# axiom_beta_plugin_module_TE0714_SDI_v0_6.net
KiCad netlist of a schematic drawn in EAGLE
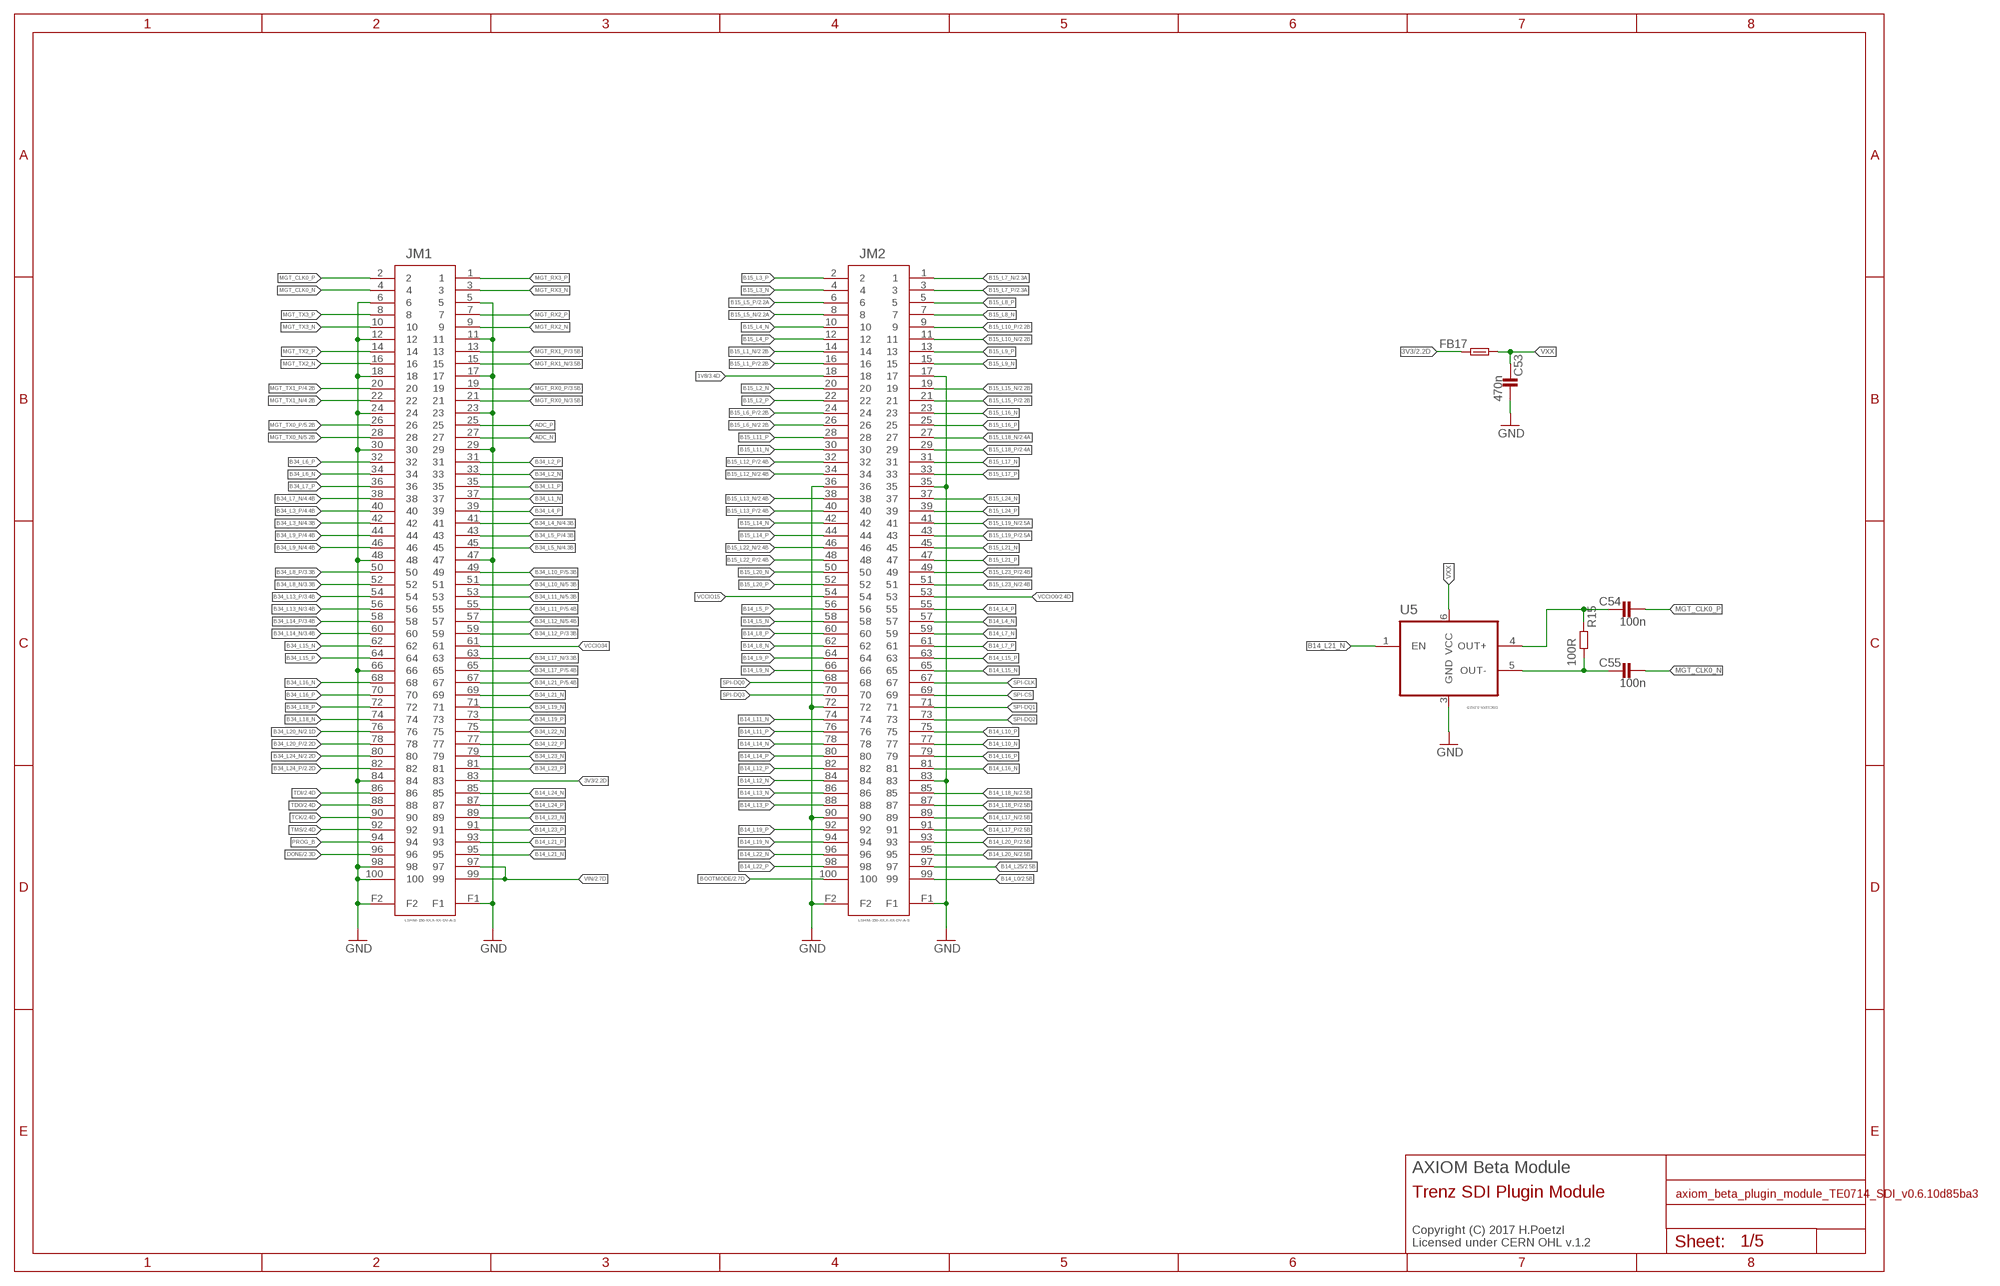
[diagram p0: schematic, sheet 1]
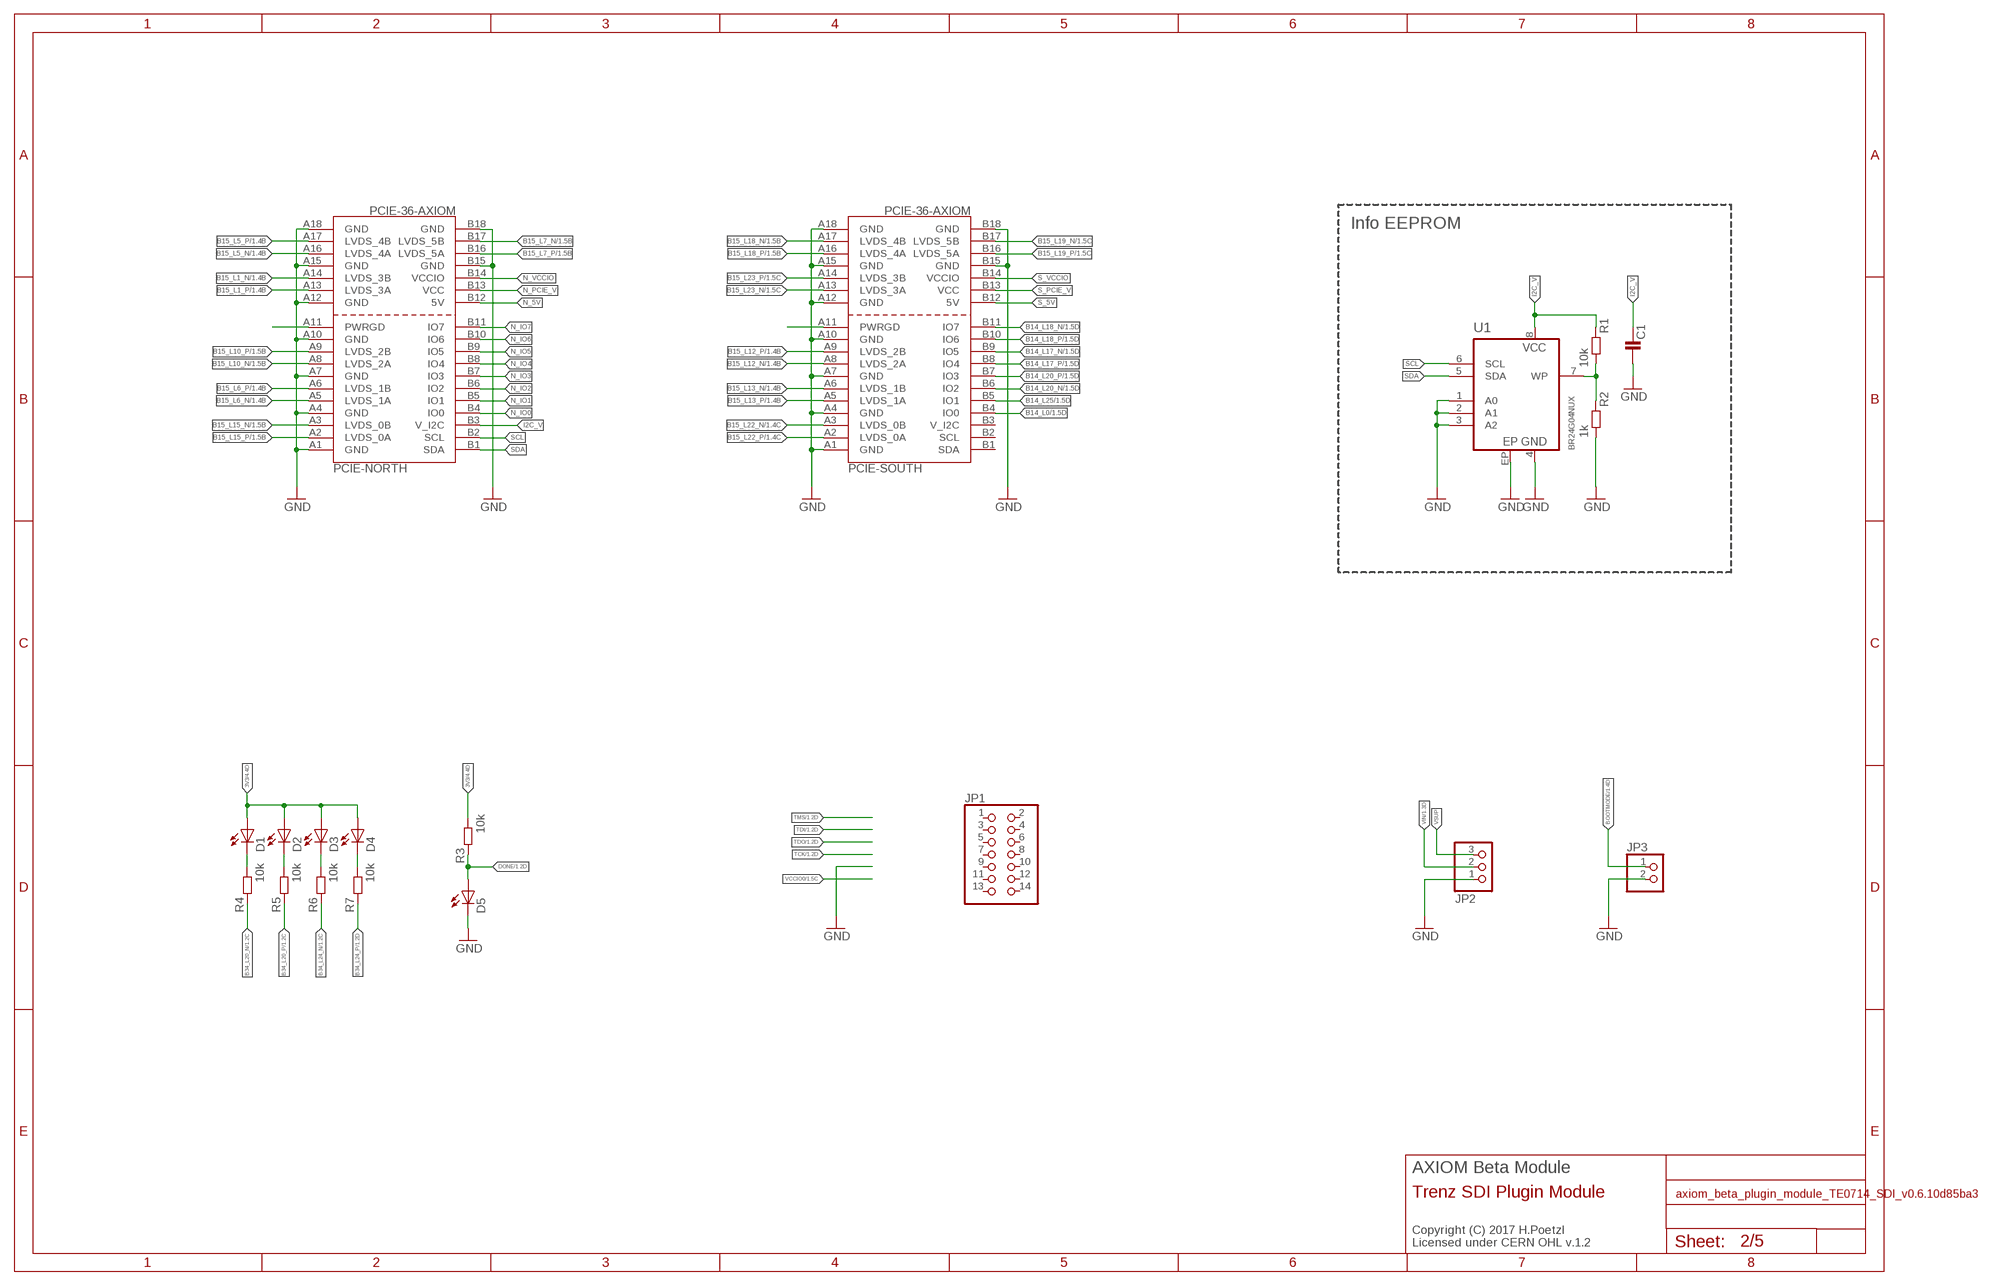
[diagram p1: schematic, sheet 2]
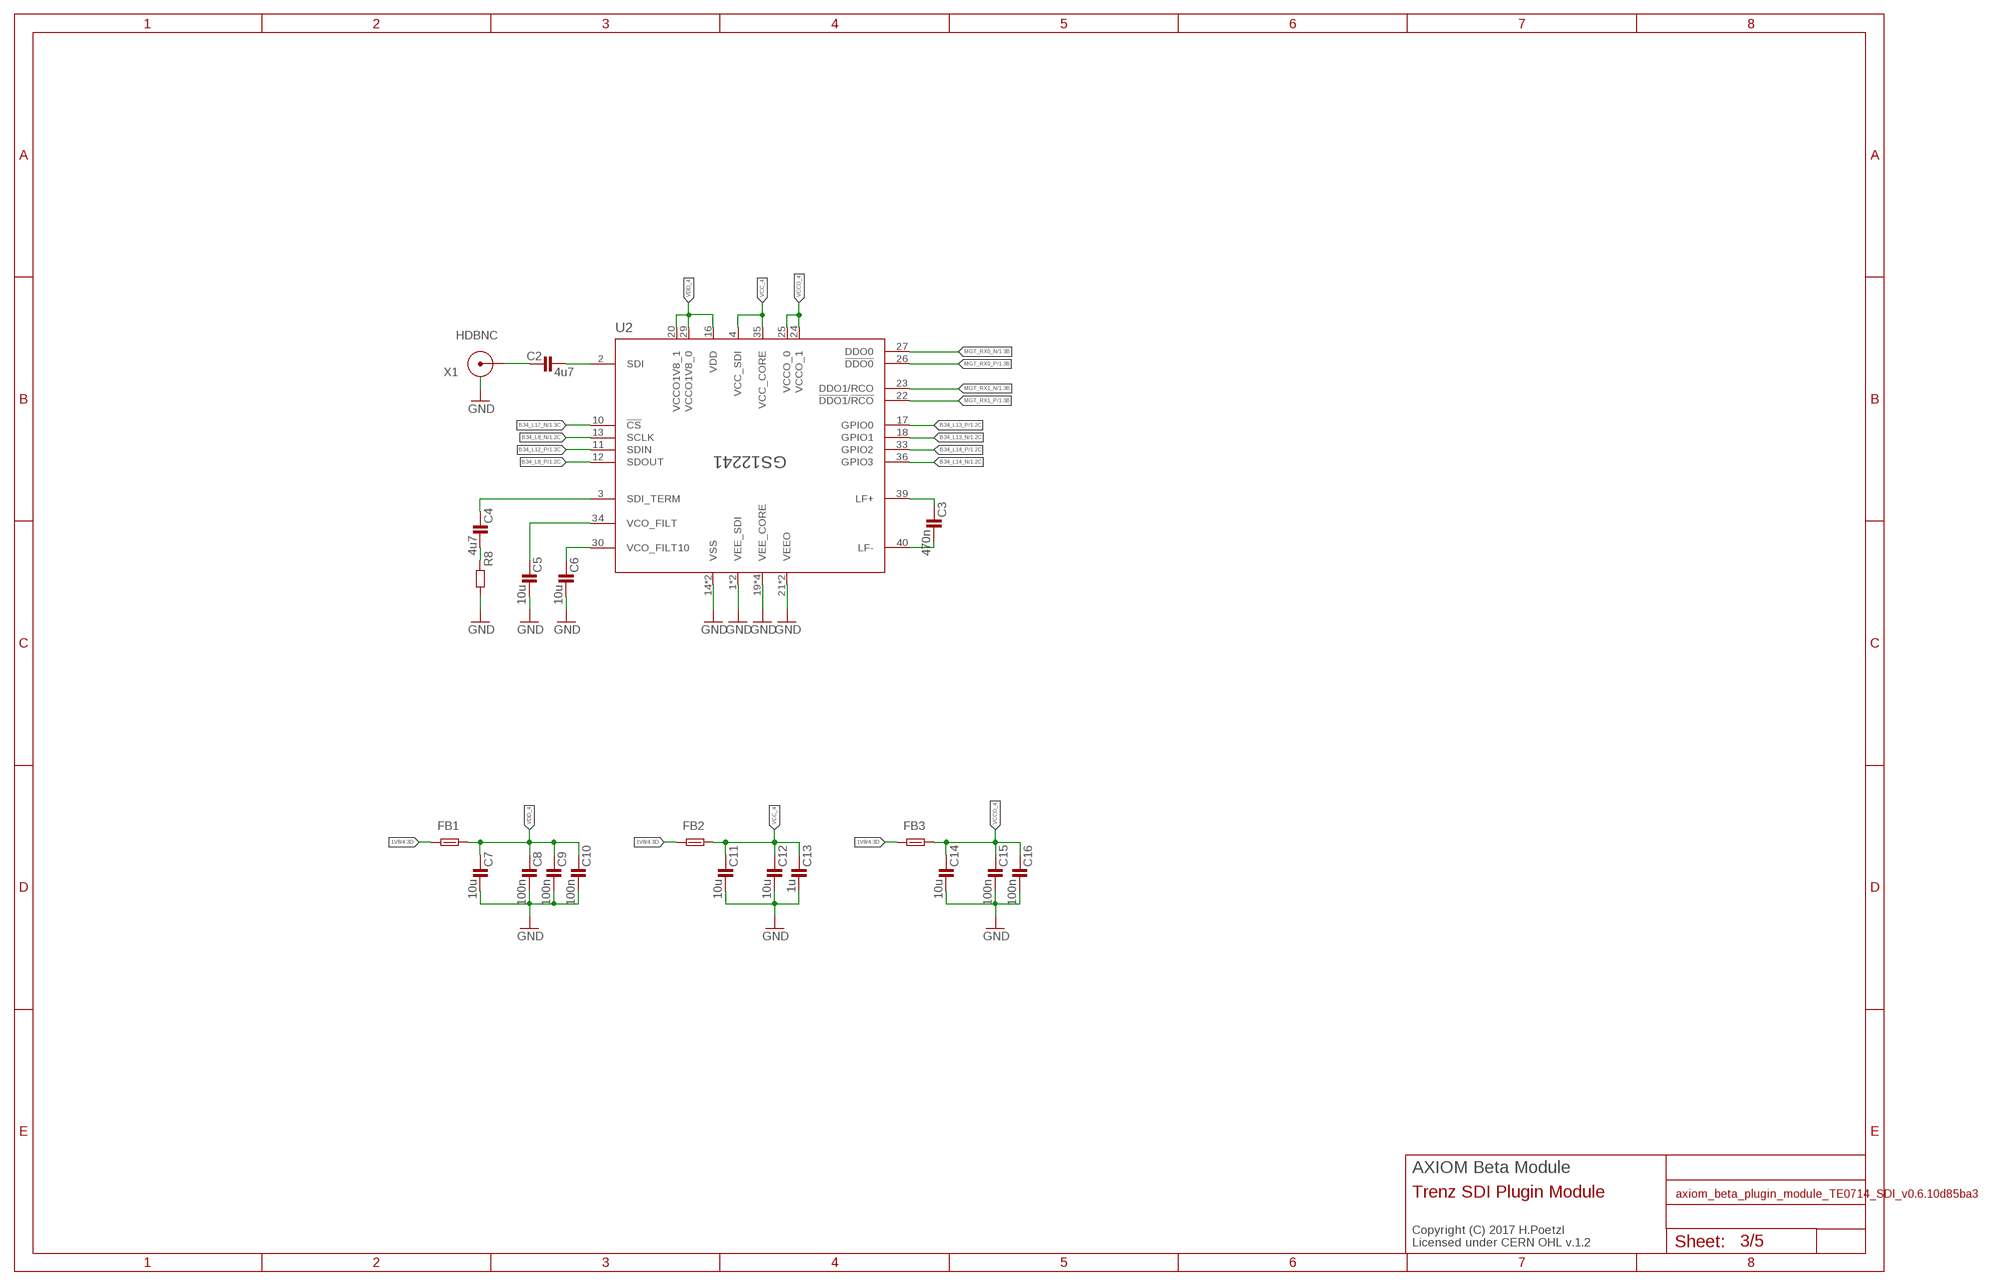
[diagram p2: schematic, sheet 3]
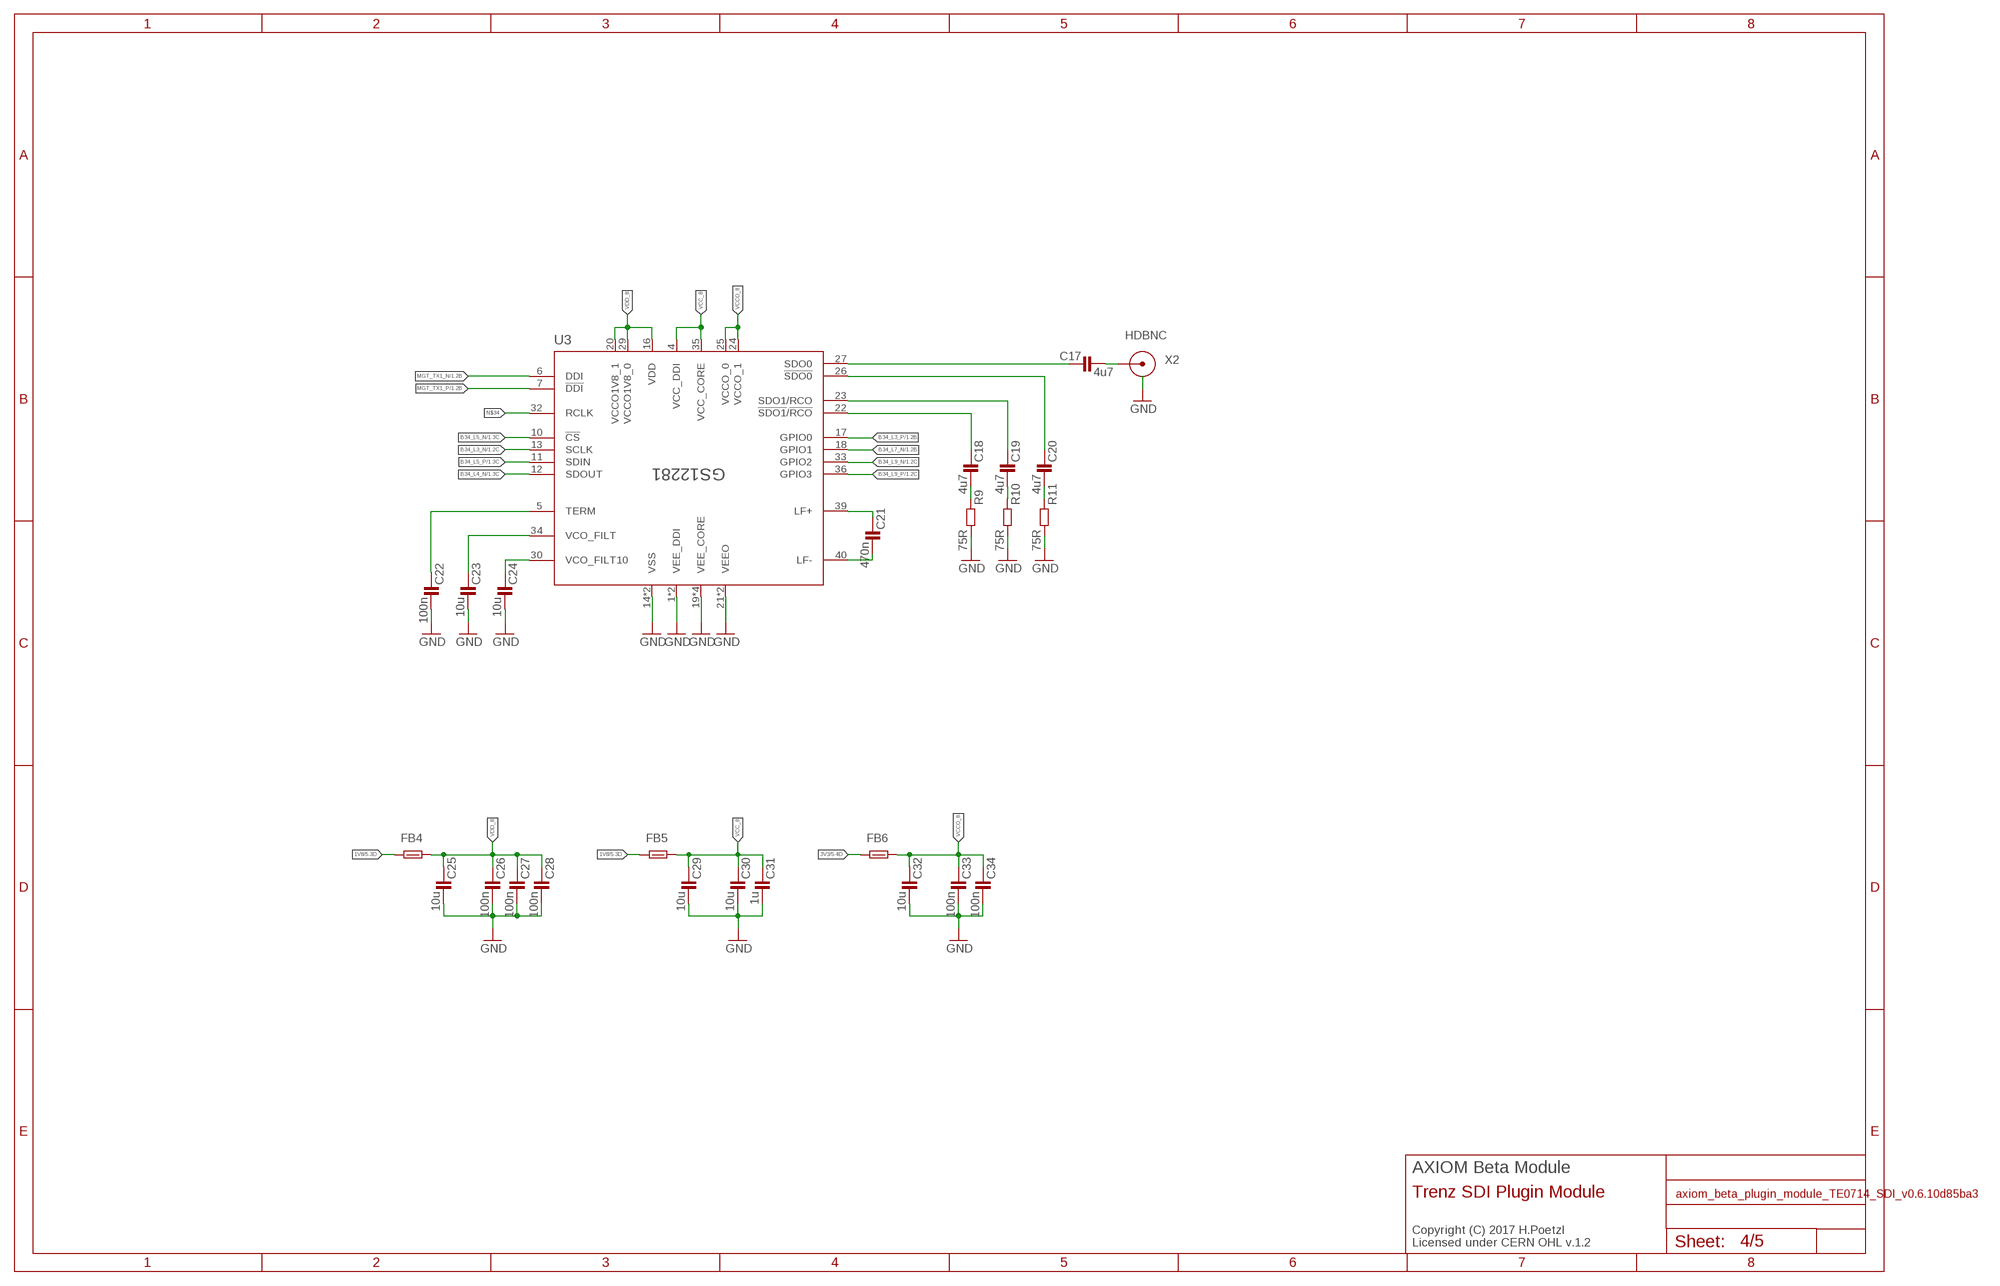
[diagram p3: schematic, sheet 4]
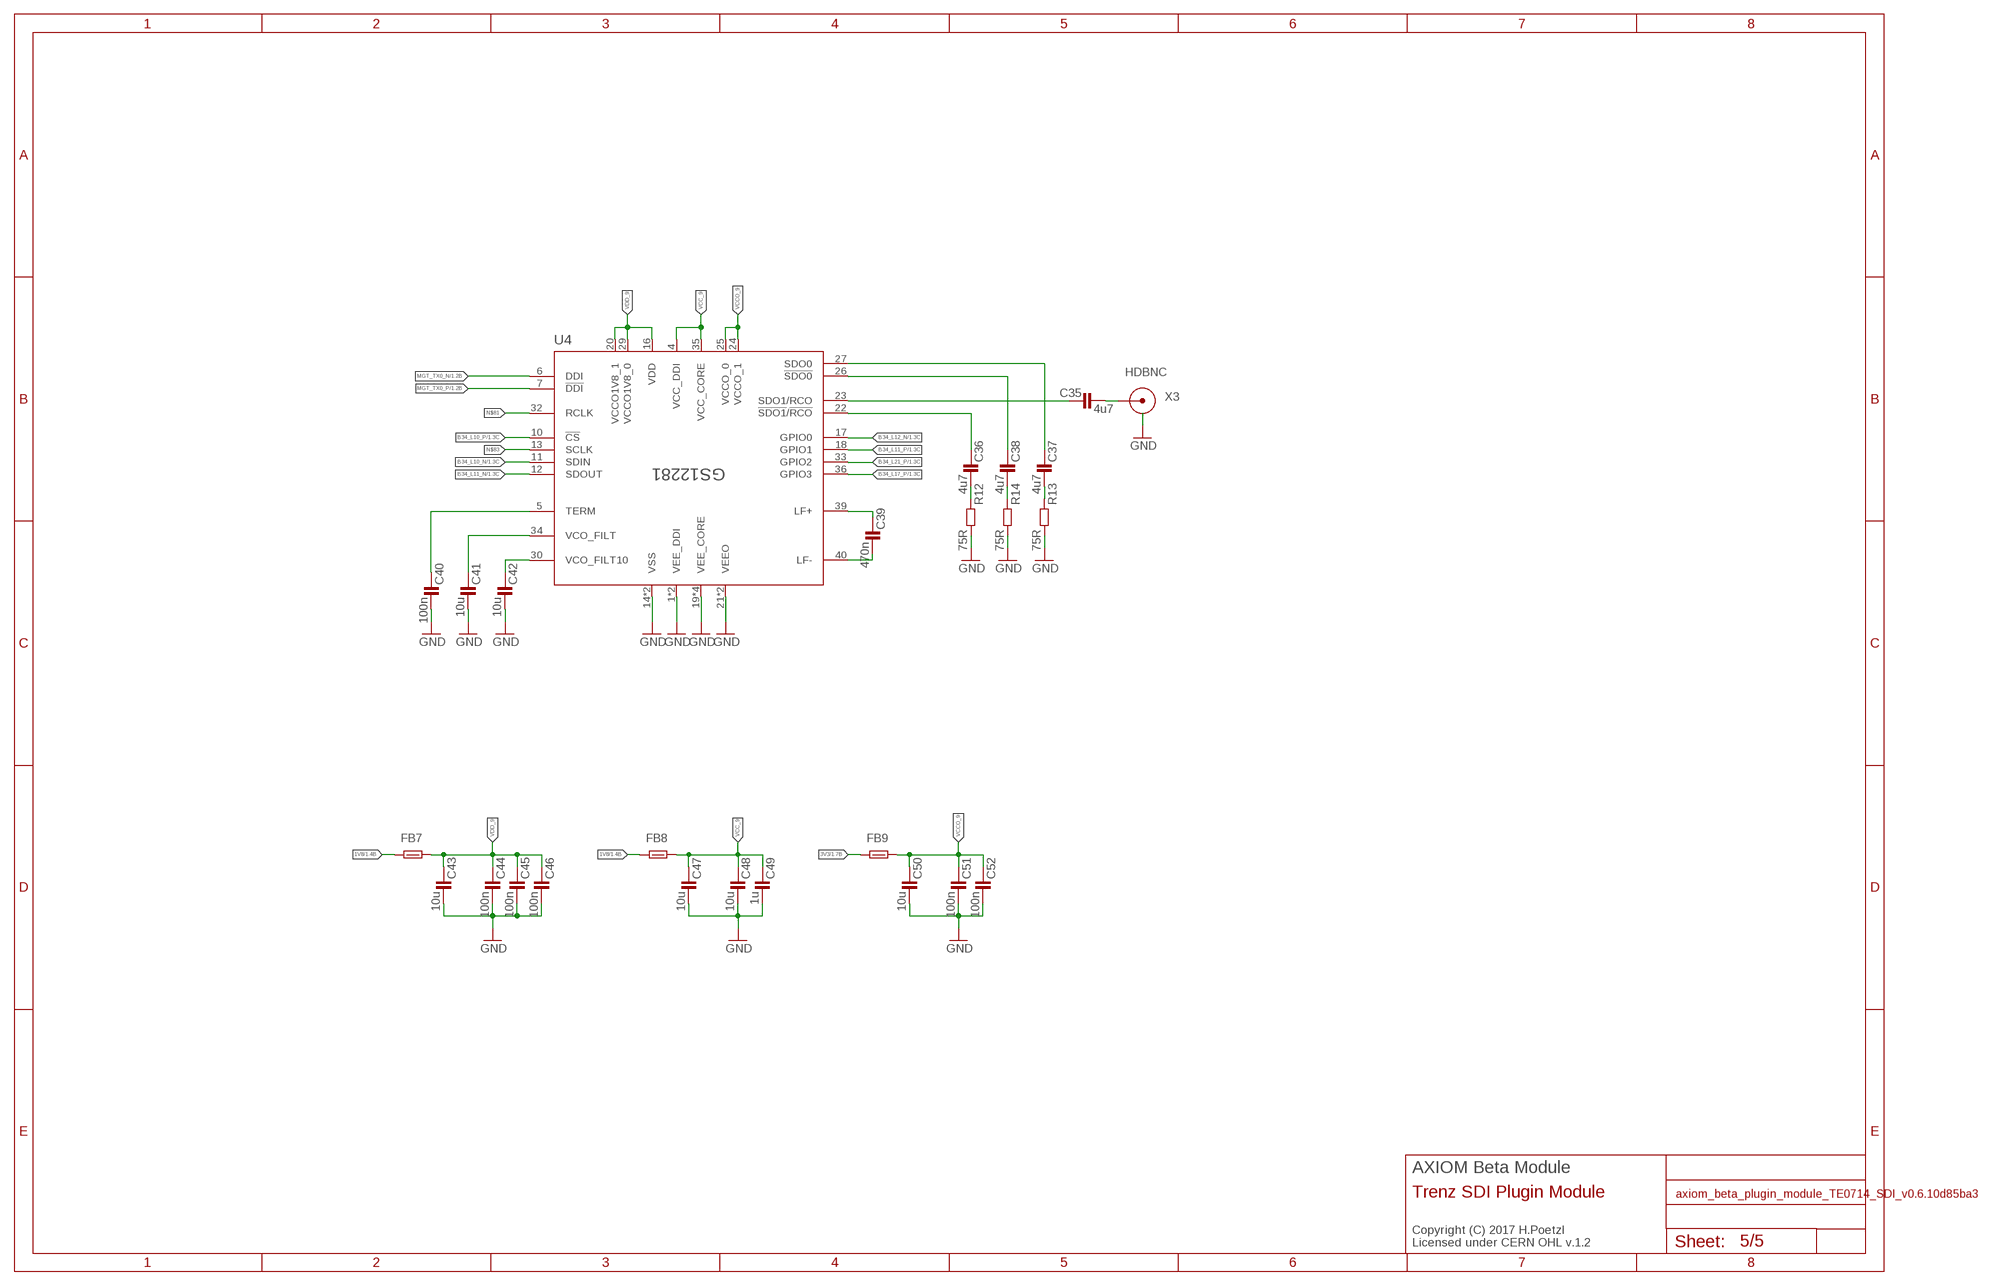
[diagram p4: schematic, sheet 5]

(export (version "E")
  (design (tool "Eeschema 10.0.6"))
  (components
    (comp (ref "C2")
      (value "4u7")
      (footprint "eagle-import:0402-C")
      (libsource (lib "eagle-import") (part "C0402-C"))
    )
    (comp (ref "C3")
      (value "470n")
      (footprint "eagle-import:0201-C")
      (libsource (lib "eagle-import") (part "C0201-C"))
    )
    (comp (ref "C4")
      (value "4u7")
      (footprint "eagle-import:0402-C")
      (libsource (lib "eagle-import") (part "C0402-C"))
    )
    (comp (ref "C5")
      (value "10u")
      (footprint "eagle-import:0201-C")
      (libsource (lib "eagle-import") (part "C0201-C"))
    )
    (comp (ref "C6")
      (value "10u")
      (footprint "eagle-import:0402-C")
      (libsource (lib "eagle-import") (part "C0402-C"))
    )
    (comp (ref "C7")
      (value "10u")
      (footprint "eagle-import:0402-C")
      (libsource (lib "eagle-import") (part "C0402-C"))
    )
    (comp (ref "C8")
      (value "100n")
      (footprint "eagle-import:0201-C")
      (libsource (lib "eagle-import") (part "C0201-C"))
    )
    (comp (ref "C9")
      (value "100n")
      (footprint "eagle-import:0201-C")
      (libsource (lib "eagle-import") (part "C0201-C"))
    )
    (comp (ref "C10")
      (value "100n")
      (footprint "eagle-import:0201-C")
      (libsource (lib "eagle-import") (part "C0201-C"))
    )
    (comp (ref "C11")
      (value "10u")
      (footprint "eagle-import:0402-C")
      (libsource (lib "eagle-import") (part "C0402-C"))
    )
    (comp (ref "C12")
      (value "10u")
      (footprint "eagle-import:0402-C")
      (libsource (lib "eagle-import") (part "C0402-C"))
    )
    (comp (ref "C13")
      (value "1u")
      (footprint "eagle-import:0201-C")
      (libsource (lib "eagle-import") (part "C0201-C"))
    )
    (comp (ref "C14")
      (value "10u")
      (footprint "eagle-import:0402-C")
      (libsource (lib "eagle-import") (part "C0402-C"))
    )
    (comp (ref "C15")
      (value "100n")
      (footprint "eagle-import:0201-C")
      (libsource (lib "eagle-import") (part "C0201-C"))
    )
    (comp (ref "C16")
      (value "100n")
      (footprint "eagle-import:0201-C")
      (libsource (lib "eagle-import") (part "C0201-C"))
    )
    (comp (ref "FB1")
      (value "FB0402-C")
      (footprint "eagle-import:0402-C")
      (libsource (lib "eagle-import") (part "FB0402-C"))
    )
    (comp (ref "FB2")
      (value "FB0402-C")
      (footprint "eagle-import:0402-C")
      (libsource (lib "eagle-import") (part "FB0402-C"))
    )
    (comp (ref "FB3")
      (value "FB0402-C")
      (footprint "eagle-import:0402-C")
      (libsource (lib "eagle-import") (part "FB0402-C"))
    )
    (comp (ref "R8")
      (value "R0201-C")
      (footprint "eagle-import:0201-C")
      (libsource (lib "eagle-import") (part "R0201-C"))
    )
    (comp (ref "U2")
      (value "GS12241")
      (footprint "eagle-import:UQFN40P600X400X100-41N")
      (libsource (lib "eagle-import") (part "GS12241"))
    )
    (comp (ref "X1")
      (value "HDBNC")
      (footprint "eagle-import:HDBNC_EDGE_2SIDE")
      (libsource (lib "eagle-import") (part "HDBNC"))
    )
    (comp (ref "C1")
      (value "C0402-B")
      (footprint "eagle-import:0402-B")
      (libsource (lib "eagle-import") (part "C0402-B"))
    )
    (comp (ref "D1")
      (value "LED")
      (footprint "eagle-import:SMARTLED-TTW")
      (libsource (lib "eagle-import") (part "LED"))
    )
    (comp (ref "D2")
      (value "LED")
      (footprint "eagle-import:SMARTLED-TTW")
      (libsource (lib "eagle-import") (part "LED"))
    )
    (comp (ref "D3")
      (value "LED")
      (footprint "eagle-import:SMARTLED-TTW")
      (libsource (lib "eagle-import") (part "LED"))
    )
    (comp (ref "D4")
      (value "LED")
      (footprint "eagle-import:SMARTLED-TTW")
      (libsource (lib "eagle-import") (part "LED"))
    )
    (comp (ref "D5")
      (value "LED")
      (footprint "eagle-import:SMARTLED-TTW")
      (libsource (lib "eagle-import") (part "LED"))
    )
    (comp (ref "JP1")
      (value "PINHD-2X07_2.00")
      (footprint "eagle-import:2X07M")
      (libsource (lib "eagle-import") (part "PINHD-2X07_2.00"))
    )
    (comp (ref "JP2")
      (value "PINHD-1X03_2.54-90°-S")
      (footprint "eagle-import:1X03_90-S")
      (libsource (lib "eagle-import") (part "PINHD-1X03_2.54-90°-S"))
    )
    (comp (ref "JP3")
      (value "PINHD-1X02_2.54-S")
      (footprint "eagle-import:1X02-S")
      (libsource (lib "eagle-import") (part "PINHD-1X02_2.54-S"))
    )
    (comp (ref "PCIE-NORTH")
      (value "PCIE-36-AXIOM")
      (footprint "eagle-import:PCIE-36-AXIOM")
      (libsource (lib "eagle-import") (part "PCIE-36-AXIOM"))
    )
    (comp (ref "PCIE-SOUTH")
      (value "PCIE-36-AXIOM")
      (footprint "eagle-import:PCIE-36-AXIOM")
      (libsource (lib "eagle-import") (part "PCIE-36-AXIOM"))
    )
    (comp (ref "R1")
      (value "10k")
      (footprint "eagle-import:0402-B")
      (libsource (lib "eagle-import") (part "R0402-B"))
    )
    (comp (ref "R2")
      (value "1k")
      (footprint "eagle-import:0402-B")
      (libsource (lib "eagle-import") (part "R0402-B"))
    )
    (comp (ref "R3")
      (value "10k")
      (footprint "eagle-import:0402-C")
      (libsource (lib "eagle-import") (part "R0402-C"))
    )
    (comp (ref "R4")
      (value "10k")
      (footprint "eagle-import:0402-C")
      (libsource (lib "eagle-import") (part "R0402-C"))
    )
    (comp (ref "R5")
      (value "10k")
      (footprint "eagle-import:0402-C")
      (libsource (lib "eagle-import") (part "R0402-C"))
    )
    (comp (ref "R6")
      (value "10k")
      (footprint "eagle-import:0402-C")
      (libsource (lib "eagle-import") (part "R0402-C"))
    )
    (comp (ref "R7")
      (value "10k")
      (footprint "eagle-import:0402-C")
      (libsource (lib "eagle-import") (part "R0402-C"))
    )
    (comp (ref "U1")
      (value "BR24G04NUX")
      (footprint "eagle-import:DFN200X300X100-9N")
      (libsource (lib "eagle-import") (part "BR24G04NUX"))
    )
    (comp (ref "C17")
      (value "4u7")
      (footprint "eagle-import:0402-C")
      (libsource (lib "eagle-import") (part "C0402-C"))
    )
    (comp (ref "C18")
      (value "4u7")
      (footprint "eagle-import:0402-C")
      (libsource (lib "eagle-import") (part "C0402-C"))
    )
    (comp (ref "C19")
      (value "4u7")
      (footprint "eagle-import:0402-C")
      (libsource (lib "eagle-import") (part "C0402-C"))
    )
    (comp (ref "C20")
      (value "4u7")
      (footprint "eagle-import:0402-C")
      (libsource (lib "eagle-import") (part "C0402-C"))
    )
    (comp (ref "C21")
      (value "470n")
      (footprint "eagle-import:0201-C")
      (libsource (lib "eagle-import") (part "C0201-C"))
    )
    (comp (ref "C22")
      (value "100n")
      (footprint "eagle-import:0201-C")
      (libsource (lib "eagle-import") (part "C0201-C"))
    )
    (comp (ref "C23")
      (value "10u")
      (footprint "eagle-import:0201-C")
      (libsource (lib "eagle-import") (part "C0201-C"))
    )
    (comp (ref "C24")
      (value "10u")
      (footprint "eagle-import:0402-C")
      (libsource (lib "eagle-import") (part "C0402-C"))
    )
    (comp (ref "C25")
      (value "10u")
      (footprint "eagle-import:0402-C")
      (libsource (lib "eagle-import") (part "C0402-C"))
    )
    (comp (ref "C26")
      (value "100n")
      (footprint "eagle-import:0201-C")
      (libsource (lib "eagle-import") (part "C0201-C"))
    )
    (comp (ref "C27")
      (value "100n")
      (footprint "eagle-import:0201-C")
      (libsource (lib "eagle-import") (part "C0201-C"))
    )
    (comp (ref "C28")
      (value "100n")
      (footprint "eagle-import:0201-C")
      (libsource (lib "eagle-import") (part "C0201-C"))
    )
    (comp (ref "C29")
      (value "10u")
      (footprint "eagle-import:0402-C")
      (libsource (lib "eagle-import") (part "C0402-C"))
    )
    (comp (ref "C30")
      (value "10u")
      (footprint "eagle-import:0402-C")
      (libsource (lib "eagle-import") (part "C0402-C"))
    )
    (comp (ref "C31")
      (value "1u")
      (footprint "eagle-import:0201-C")
      (libsource (lib "eagle-import") (part "C0201-C"))
    )
    (comp (ref "C32")
      (value "10u")
      (footprint "eagle-import:0402-C")
      (libsource (lib "eagle-import") (part "C0402-C"))
    )
    (comp (ref "C33")
      (value "100n")
      (footprint "eagle-import:0201-C")
      (libsource (lib "eagle-import") (part "C0201-C"))
    )
    (comp (ref "C34")
      (value "100n")
      (footprint "eagle-import:0201-C")
      (libsource (lib "eagle-import") (part "C0201-C"))
    )
    (comp (ref "FB4")
      (value "FB0402-C")
      (footprint "eagle-import:0402-C")
      (libsource (lib "eagle-import") (part "FB0402-C"))
    )
    (comp (ref "FB5")
      (value "FB0402-C")
      (footprint "eagle-import:0402-C")
      (libsource (lib "eagle-import") (part "FB0402-C"))
    )
    (comp (ref "FB6")
      (value "FB0402-C")
      (footprint "eagle-import:0402-C")
      (libsource (lib "eagle-import") (part "FB0402-C"))
    )
    (comp (ref "R9")
      (value "75R")
      (footprint "eagle-import:0201-C")
      (libsource (lib "eagle-import") (part "R0201-C"))
    )
    (comp (ref "R10")
      (value "75R")
      (footprint "eagle-import:0201-C")
      (libsource (lib "eagle-import") (part "R0201-C"))
    )
    (comp (ref "R11")
      (value "75R")
      (footprint "eagle-import:0201-C")
      (libsource (lib "eagle-import") (part "R0201-C"))
    )
    (comp (ref "U3")
      (value "GS12281")
      (footprint "eagle-import:UQFN40P600X400X100-41N")
      (libsource (lib "eagle-import") (part "GS12281"))
    )
    (comp (ref "X2")
      (value "HDBNC")
      (footprint "eagle-import:HDBNC_EDGE_2SIDE")
      (libsource (lib "eagle-import") (part "HDBNC"))
    )
    (comp (ref "C35")
      (value "4u7")
      (footprint "eagle-import:0402-C")
      (libsource (lib "eagle-import") (part "C0402-C"))
    )
    (comp (ref "C36")
      (value "4u7")
      (footprint "eagle-import:0402-C")
      (libsource (lib "eagle-import") (part "C0402-C"))
    )
    (comp (ref "C37")
      (value "4u7")
      (footprint "eagle-import:0402-C")
      (libsource (lib "eagle-import") (part "C0402-C"))
    )
    (comp (ref "C38")
      (value "4u7")
      (footprint "eagle-import:0402-C")
      (libsource (lib "eagle-import") (part "C0402-C"))
    )
    (comp (ref "C39")
      (value "470n")
      (footprint "eagle-import:0201-C")
      (libsource (lib "eagle-import") (part "C0201-C"))
    )
    (comp (ref "C40")
      (value "100n")
      (footprint "eagle-import:0201-C")
      (libsource (lib "eagle-import") (part "C0201-C"))
    )
    (comp (ref "C41")
      (value "10u")
      (footprint "eagle-import:0402-C")
      (libsource (lib "eagle-import") (part "C0402-C"))
    )
    (comp (ref "C42")
      (value "10u")
      (footprint "eagle-import:0402-C")
      (libsource (lib "eagle-import") (part "C0402-C"))
    )
    (comp (ref "C43")
      (value "10u")
      (footprint "eagle-import:0402-C")
      (libsource (lib "eagle-import") (part "C0402-C"))
    )
    (comp (ref "C44")
      (value "100n")
      (footprint "eagle-import:0201-C")
      (libsource (lib "eagle-import") (part "C0201-C"))
    )
    (comp (ref "C45")
      (value "100n")
      (footprint "eagle-import:0201-C")
      (libsource (lib "eagle-import") (part "C0201-C"))
    )
    (comp (ref "C46")
      (value "100n")
      (footprint "eagle-import:0201-C")
      (libsource (lib "eagle-import") (part "C0201-C"))
    )
    (comp (ref "C47")
      (value "10u")
      (footprint "eagle-import:0402-C")
      (libsource (lib "eagle-import") (part "C0402-C"))
    )
    (comp (ref "C48")
      (value "10u")
      (footprint "eagle-import:0402-C")
      (libsource (lib "eagle-import") (part "C0402-C"))
    )
    (comp (ref "C49")
      (value "1u")
      (footprint "eagle-import:0201-C")
      (libsource (lib "eagle-import") (part "C0201-C"))
    )
    (comp (ref "C50")
      (value "10u")
      (footprint "eagle-import:0402-C")
      (libsource (lib "eagle-import") (part "C0402-C"))
    )
    (comp (ref "C51")
      (value "100n")
      (footprint "eagle-import:0201-C")
      (libsource (lib "eagle-import") (part "C0201-C"))
    )
    (comp (ref "C52")
      (value "100n")
      (footprint "eagle-import:0201-C")
      (libsource (lib "eagle-import") (part "C0201-C"))
    )
    (comp (ref "FB7")
      (value "FB0402-C")
      (footprint "eagle-import:0402-C")
      (libsource (lib "eagle-import") (part "FB0402-C"))
    )
    (comp (ref "FB8")
      (value "FB0402-C")
      (footprint "eagle-import:0402-C")
      (libsource (lib "eagle-import") (part "FB0402-C"))
    )
    (comp (ref "FB9")
      (value "FB0402-C")
      (footprint "eagle-import:0402-C")
      (libsource (lib "eagle-import") (part "FB0402-C"))
    )
    (comp (ref "R12")
      (value "75R")
      (footprint "eagle-import:0201-C")
      (libsource (lib "eagle-import") (part "R0201-C"))
    )
    (comp (ref "R13")
      (value "75R")
      (footprint "eagle-import:0201-C")
      (libsource (lib "eagle-import") (part "R0201-C"))
    )
    (comp (ref "R14")
      (value "75R")
      (footprint "eagle-import:0201-C")
      (libsource (lib "eagle-import") (part "R0201-C"))
    )
    (comp (ref "U4")
      (value "GS12281")
      (footprint "eagle-import:UQFN40P600X400X100-41N")
      (libsource (lib "eagle-import") (part "GS12281"))
    )
    (comp (ref "X3")
      (value "HDBNC")
      (footprint "eagle-import:HDBNC_EDGE_2SIDE")
      (libsource (lib "eagle-import") (part "HDBNC"))
    )
    (comp (ref "C53")
      (value "470n")
      (footprint "eagle-import:0402-C")
      (libsource (lib "eagle-import") (part "C0402-C"))
    )
    (comp (ref "C54")
      (value "100n")
      (footprint "eagle-import:0201-C")
      (libsource (lib "eagle-import") (part "C0201-C"))
    )
    (comp (ref "C55")
      (value "100n")
      (footprint "eagle-import:0201-C")
      (libsource (lib "eagle-import") (part "C0201-C"))
    )
    (comp (ref "FB17")
      (value "FB0402-C")
      (footprint "eagle-import:0402-C")
      (libsource (lib "eagle-import") (part "FB0402-C"))
    )
    (comp (ref "JM1")
      (value "LSHM-150-XX.X-XX-DV-A-S")
      (footprint "eagle-import:LSHM-150-XX.X-XX-DV-A-S")
      (libsource (lib "eagle-import") (part "LSHM-150-XX.X-XX-DV-A-S"))
    )
    (comp (ref "JM2")
      (value "LSHM-150-XX.X-XX-DV-A-S")
      (footprint "eagle-import:LSHM-150-XX.X-XX-DV-A-S")
      (libsource (lib "eagle-import") (part "LSHM-150-XX.X-XX-DV-A-S"))
    )
    (comp (ref "R15")
      (value "100R")
      (footprint "eagle-import:0201-C")
      (libsource (lib "eagle-import") (part "R0201-C"))
    )
    (comp (ref "U5")
      (value "DSC11XX-3.2X2.5")
      (footprint "eagle-import:3.2X2.5")
      (libsource (lib "eagle-import") (part "DSC11XX-3.2X2.5"))
    )
  )
  (nets
    (net (code "1") (name "1V8") (class "Default")
      (node (ref "FB1") (pin "1") (pinfunction "1_1") (pintype "passive"))
      (node (ref "FB2") (pin "1") (pinfunction "1_1") (pintype "passive"))
      (node (ref "FB3") (pin "1") (pinfunction "1_1") (pintype "passive"))
      (node (ref "FB4") (pin "1") (pinfunction "1_1") (pintype "passive"))
      (node (ref "FB5") (pin "1") (pinfunction "1_1") (pintype "passive"))
      (node (ref "FB7") (pin "1") (pinfunction "1_1") (pintype "passive"))
      (node (ref "FB8") (pin "1") (pinfunction "1_1") (pintype "passive"))
      (node (ref "JM2") (pin "18") (pinfunction "18_18") (pintype "bidirectional"))
    )
    (net (code "2") (name "3V3") (class "Default")
      (node (ref "D1") (pin "A@1") (pinfunction "A_A@1") (pintype "passive"))
      (node (ref "D2") (pin "A@1") (pinfunction "A_A@1") (pintype "passive"))
      (node (ref "D3") (pin "A@1") (pinfunction "A_A@1") (pintype "passive"))
      (node (ref "D4") (pin "A@1") (pinfunction "A_A@1") (pintype "passive"))
      (node (ref "FB17") (pin "1") (pinfunction "1_1") (pintype "passive"))
      (node (ref "FB6") (pin "1") (pinfunction "1_1") (pintype "passive"))
      (node (ref "FB9") (pin "1") (pinfunction "1_1") (pintype "passive"))
      (node (ref "JM1") (pin "83") (pinfunction "83_83") (pintype "bidirectional"))
      (node (ref "R3") (pin "2") (pinfunction "2_2") (pintype "passive"))
    )
    (net (code "3") (name "ADC_N") (class "Default")
      (node (ref "JM1") (pin "27") (pinfunction "27_27") (pintype "bidirectional"))
    )
    (net (code "4") (name "ADC_P") (class "Default")
      (node (ref "JM1") (pin "25") (pinfunction "25_25") (pintype "bidirectional"))
    )
    (net (code "5") (name "B14_L0") (class "Default")
      (node (ref "JM2") (pin "99") (pinfunction "99_99") (pintype "bidirectional"))
      (node (ref "PCIE-SOUTH") (pin "B4") (pinfunction "IO0_B4") (pintype "passive"))
    )
    (net (code "6") (name "B14_L4_N") (class "Default")
      (node (ref "JM2") (pin "57") (pinfunction "57_57") (pintype "bidirectional"))
    )
    (net (code "7") (name "B14_L4_P") (class "Default")
      (node (ref "JM2") (pin "55") (pinfunction "55_55") (pintype "bidirectional"))
    )
    (net (code "8") (name "B14_L5_N") (class "Default")
      (node (ref "JM2") (pin "58") (pinfunction "58_58") (pintype "bidirectional"))
    )
    (net (code "9") (name "B14_L5_P") (class "Default")
      (node (ref "JM2") (pin "56") (pinfunction "56_56") (pintype "bidirectional"))
    )
    (net (code "10") (name "B14_L7_N") (class "Default")
      (node (ref "JM2") (pin "59") (pinfunction "59_59") (pintype "bidirectional"))
    )
    (net (code "11") (name "B14_L7_P") (class "Default")
      (node (ref "JM2") (pin "61") (pinfunction "61_61") (pintype "bidirectional"))
    )
    (net (code "12") (name "B14_L8_N") (class "Default")
      (node (ref "JM2") (pin "62") (pinfunction "62_62") (pintype "bidirectional"))
    )
    (net (code "13") (name "B14_L8_P") (class "Default")
      (node (ref "JM2") (pin "60") (pinfunction "60_60") (pintype "bidirectional"))
    )
    (net (code "14") (name "B14_L9_N") (class "Default")
      (node (ref "JM2") (pin "66") (pinfunction "66_66") (pintype "bidirectional"))
    )
    (net (code "15") (name "B14_L9_P") (class "Default")
      (node (ref "JM2") (pin "64") (pinfunction "64_64") (pintype "bidirectional"))
    )
    (net (code "16") (name "B14_L10_N") (class "Default")
      (node (ref "JM2") (pin "77") (pinfunction "77_77") (pintype "bidirectional"))
    )
    (net (code "17") (name "B14_L10_P") (class "Default")
      (node (ref "JM2") (pin "75") (pinfunction "75_75") (pintype "bidirectional"))
    )
    (net (code "18") (name "B14_L11_N") (class "Default")
      (node (ref "JM2") (pin "74") (pinfunction "74_74") (pintype "bidirectional"))
    )
    (net (code "19") (name "B14_L11_P") (class "Default")
      (node (ref "JM2") (pin "76") (pinfunction "76_76") (pintype "bidirectional"))
    )
    (net (code "20") (name "B14_L12_N") (class "Default")
      (node (ref "JM2") (pin "84") (pinfunction "84_84") (pintype "bidirectional"))
    )
    (net (code "21") (name "B14_L12_P") (class "Default")
      (node (ref "JM2") (pin "82") (pinfunction "82_82") (pintype "bidirectional"))
    )
    (net (code "22") (name "B14_L13_N") (class "Default")
      (node (ref "JM2") (pin "86") (pinfunction "86_86") (pintype "bidirectional"))
    )
    (net (code "23") (name "B14_L13_P") (class "Default")
      (node (ref "JM2") (pin "88") (pinfunction "88_88") (pintype "bidirectional"))
    )
    (net (code "24") (name "B14_L14_N") (class "Default")
      (node (ref "JM2") (pin "78") (pinfunction "78_78") (pintype "bidirectional"))
    )
    (net (code "25") (name "B14_L14_P") (class "Default")
      (node (ref "JM2") (pin "80") (pinfunction "80_80") (pintype "bidirectional"))
    )
    (net (code "26") (name "B14_L15_N") (class "Default")
      (node (ref "JM2") (pin "65") (pinfunction "65_65") (pintype "bidirectional"))
    )
    (net (code "27") (name "B14_L15_P") (class "Default")
      (node (ref "JM2") (pin "63") (pinfunction "63_63") (pintype "bidirectional"))
    )
    (net (code "28") (name "B14_L16_N") (class "Default")
      (node (ref "JM2") (pin "81") (pinfunction "81_81") (pintype "bidirectional"))
    )
    (net (code "29") (name "B14_L16_P") (class "Default")
      (node (ref "JM2") (pin "79") (pinfunction "79_79") (pintype "bidirectional"))
    )
    (net (code "30") (name "B14_L17_N") (class "Default")
      (node (ref "JM2") (pin "89") (pinfunction "89_89") (pintype "bidirectional"))
      (node (ref "PCIE-SOUTH") (pin "B9") (pinfunction "IO5_B9") (pintype "passive"))
    )
    (net (code "31") (name "B14_L17_P") (class "Default")
      (node (ref "JM2") (pin "91") (pinfunction "91_91") (pintype "bidirectional"))
      (node (ref "PCIE-SOUTH") (pin "B8") (pinfunction "IO4_B8") (pintype "passive"))
    )
    (net (code "32") (name "B14_L18_N") (class "Default")
      (node (ref "JM2") (pin "85") (pinfunction "85_85") (pintype "bidirectional"))
      (node (ref "PCIE-SOUTH") (pin "B11") (pinfunction "IO7_B11") (pintype "passive"))
    )
    (net (code "33") (name "B14_L18_P") (class "Default")
      (node (ref "JM2") (pin "87") (pinfunction "87_87") (pintype "bidirectional"))
      (node (ref "PCIE-SOUTH") (pin "B10") (pinfunction "IO6_B10") (pintype "passive"))
    )
    (net (code "34") (name "B14_L19_N") (class "Default")
      (node (ref "JM2") (pin "94") (pinfunction "94_94") (pintype "bidirectional"))
    )
    (net (code "35") (name "B14_L19_P") (class "Default")
      (node (ref "JM2") (pin "92") (pinfunction "92_92") (pintype "bidirectional"))
    )
    (net (code "36") (name "B14_L20_N") (class "Default")
      (node (ref "JM2") (pin "95") (pinfunction "95_95") (pintype "bidirectional"))
      (node (ref "PCIE-SOUTH") (pin "B6") (pinfunction "IO2_B6") (pintype "passive"))
    )
    (net (code "37") (name "B14_L20_P") (class "Default")
      (node (ref "JM2") (pin "93") (pinfunction "93_93") (pintype "bidirectional"))
      (node (ref "PCIE-SOUTH") (pin "B7") (pinfunction "IO3_B7") (pintype "passive"))
    )
    (net (code "38") (name "B14_L21_N") (class "Default")
      (node (ref "JM1") (pin "95") (pinfunction "95_95") (pintype "bidirectional"))
      (node (ref "U5") (pin "1") (pinfunction "EN_1") (pintype "input"))
    )
    (net (code "39") (name "B14_L21_P") (class "Default")
      (node (ref "JM1") (pin "93") (pinfunction "93_93") (pintype "bidirectional"))
    )
    (net (code "40") (name "B14_L22_N") (class "Default")
      (node (ref "JM2") (pin "96") (pinfunction "96_96") (pintype "bidirectional"))
    )
    (net (code "41") (name "B14_L22_P") (class "Default")
      (node (ref "JM2") (pin "98") (pinfunction "98_98") (pintype "bidirectional"))
    )
    (net (code "42") (name "B14_L23_N") (class "Default")
      (node (ref "JM1") (pin "89") (pinfunction "89_89") (pintype "bidirectional"))
    )
    (net (code "43") (name "B14_L23_P") (class "Default")
      (node (ref "JM1") (pin "91") (pinfunction "91_91") (pintype "bidirectional"))
    )
    (net (code "44") (name "B14_L24_N") (class "Default")
      (node (ref "JM1") (pin "85") (pinfunction "85_85") (pintype "bidirectional"))
    )
    (net (code "45") (name "B14_L24_P") (class "Default")
      (node (ref "JM1") (pin "87") (pinfunction "87_87") (pintype "bidirectional"))
    )
    (net (code "46") (name "B14_L25") (class "Default")
      (node (ref "JM2") (pin "97") (pinfunction "97_97") (pintype "bidirectional"))
      (node (ref "PCIE-SOUTH") (pin "B5") (pinfunction "IO1_B5") (pintype "passive"))
    )
    (net (code "47") (name "B15_L1_N") (class "Default")
      (node (ref "JM2") (pin "14") (pinfunction "14_14") (pintype "bidirectional"))
      (node (ref "PCIE-NORTH") (pin "A14") (pinfunction "LVDS_3B_A14") (pintype "passive"))
    )
    (net (code "48") (name "B15_L1_P") (class "Default")
      (node (ref "JM2") (pin "16") (pinfunction "16_16") (pintype "bidirectional"))
      (node (ref "PCIE-NORTH") (pin "A13") (pinfunction "LVDS_3A_A13") (pintype "passive"))
    )
    (net (code "49") (name "B15_L2_N") (class "Default")
      (node (ref "JM2") (pin "20") (pinfunction "20_20") (pintype "bidirectional"))
    )
    (net (code "50") (name "B15_L2_P") (class "Default")
      (node (ref "JM2") (pin "22") (pinfunction "22_22") (pintype "bidirectional"))
    )
    (net (code "51") (name "B15_L3_N") (class "Default")
      (node (ref "JM2") (pin "4") (pinfunction "4_4") (pintype "bidirectional"))
    )
    (net (code "52") (name "B15_L3_P") (class "Default")
      (node (ref "JM2") (pin "2") (pinfunction "2_2") (pintype "bidirectional"))
    )
    (net (code "53") (name "B15_L4_N") (class "Default")
      (node (ref "JM2") (pin "10") (pinfunction "10_10") (pintype "bidirectional"))
    )
    (net (code "54") (name "B15_L4_P") (class "Default")
      (node (ref "JM2") (pin "12") (pinfunction "12_12") (pintype "bidirectional"))
    )
    (net (code "55") (name "B15_L5_N") (class "Default")
      (node (ref "JM2") (pin "8") (pinfunction "8_8") (pintype "bidirectional"))
      (node (ref "PCIE-NORTH") (pin "A16") (pinfunction "LVDS_4A_A16") (pintype "passive"))
    )
    (net (code "56") (name "B15_L5_P") (class "Default")
      (node (ref "JM2") (pin "6") (pinfunction "6_6") (pintype "bidirectional"))
      (node (ref "PCIE-NORTH") (pin "A17") (pinfunction "LVDS_4B_A17") (pintype "passive"))
    )
    (net (code "57") (name "B15_L6_N") (class "Default")
      (node (ref "JM2") (pin "26") (pinfunction "26_26") (pintype "bidirectional"))
      (node (ref "PCIE-NORTH") (pin "A5") (pinfunction "LVDS_1A_A5") (pintype "passive"))
    )
    (net (code "58") (name "B15_L6_P") (class "Default")
      (node (ref "JM2") (pin "24") (pinfunction "24_24") (pintype "bidirectional"))
      (node (ref "PCIE-NORTH") (pin "A6") (pinfunction "LVDS_1B_A6") (pintype "passive"))
    )
    (net (code "59") (name "B15_L7_N") (class "Default")
      (node (ref "JM2") (pin "1") (pinfunction "1_1") (pintype "bidirectional"))
      (node (ref "PCIE-NORTH") (pin "B17") (pinfunction "LVDS_5B_B17") (pintype "passive"))
    )
    (net (code "60") (name "B15_L7_P") (class "Default")
      (node (ref "JM2") (pin "3") (pinfunction "3_3") (pintype "bidirectional"))
      (node (ref "PCIE-NORTH") (pin "B16") (pinfunction "LVDS_5A_B16") (pintype "passive"))
    )
    (net (code "61") (name "B15_L8_N") (class "Default")
      (node (ref "JM2") (pin "7") (pinfunction "7_7") (pintype "bidirectional"))
    )
    (net (code "62") (name "B15_L8_P") (class "Default")
      (node (ref "JM2") (pin "5") (pinfunction "5_5") (pintype "bidirectional"))
    )
    (net (code "63") (name "B15_L9_N") (class "Default")
      (node (ref "JM2") (pin "15") (pinfunction "15_15") (pintype "bidirectional"))
    )
    (net (code "64") (name "B15_L9_P") (class "Default")
      (node (ref "JM2") (pin "13") (pinfunction "13_13") (pintype "bidirectional"))
    )
    (net (code "65") (name "B15_L10_N") (class "Default")
      (node (ref "JM2") (pin "11") (pinfunction "11_11") (pintype "bidirectional"))
      (node (ref "PCIE-NORTH") (pin "A8") (pinfunction "LVDS_2A_A8") (pintype "passive"))
    )
    (net (code "66") (name "B15_L10_P") (class "Default")
      (node (ref "JM2") (pin "9") (pinfunction "9_9") (pintype "bidirectional"))
      (node (ref "PCIE-NORTH") (pin "A9") (pinfunction "LVDS_2B_A9") (pintype "passive"))
    )
    (net (code "67") (name "B15_L11_N") (class "Default")
      (node (ref "JM2") (pin "30") (pinfunction "30_30") (pintype "bidirectional"))
    )
    (net (code "68") (name "B15_L11_P") (class "Default")
      (node (ref "JM2") (pin "28") (pinfunction "28_28") (pintype "bidirectional"))
    )
    (net (code "69") (name "B15_L12_N") (class "Default")
      (node (ref "JM2") (pin "34") (pinfunction "34_34") (pintype "bidirectional"))
      (node (ref "PCIE-SOUTH") (pin "A8") (pinfunction "LVDS_2A_A8") (pintype "passive"))
    )
    (net (code "70") (name "B15_L12_P") (class "Default")
      (node (ref "JM2") (pin "32") (pinfunction "32_32") (pintype "bidirectional"))
      (node (ref "PCIE-SOUTH") (pin "A9") (pinfunction "LVDS_2B_A9") (pintype "passive"))
    )
    (net (code "71") (name "B15_L13_N") (class "Default")
      (node (ref "JM2") (pin "38") (pinfunction "38_38") (pintype "bidirectional"))
      (node (ref "PCIE-SOUTH") (pin "A6") (pinfunction "LVDS_1B_A6") (pintype "passive"))
    )
    (net (code "72") (name "B15_L13_P") (class "Default")
      (node (ref "JM2") (pin "40") (pinfunction "40_40") (pintype "bidirectional"))
      (node (ref "PCIE-SOUTH") (pin "A5") (pinfunction "LVDS_1A_A5") (pintype "passive"))
    )
    (net (code "73") (name "B15_L14_N") (class "Default")
      (node (ref "JM2") (pin "42") (pinfunction "42_42") (pintype "bidirectional"))
    )
    (net (code "74") (name "B15_L14_P") (class "Default")
      (node (ref "JM2") (pin "44") (pinfunction "44_44") (pintype "bidirectional"))
    )
    (net (code "75") (name "B15_L15_N") (class "Default")
      (node (ref "JM2") (pin "19") (pinfunction "19_19") (pintype "bidirectional"))
      (node (ref "PCIE-NORTH") (pin "A3") (pinfunction "LVDS_0B_A3") (pintype "passive"))
    )
    (net (code "76") (name "B15_L15_P") (class "Default")
      (node (ref "JM2") (pin "21") (pinfunction "21_21") (pintype "bidirectional"))
      (node (ref "PCIE-NORTH") (pin "A2") (pinfunction "LVDS_0A_A2") (pintype "passive"))
    )
    (net (code "77") (name "B15_L16_N") (class "Default")
      (node (ref "JM2") (pin "23") (pinfunction "23_23") (pintype "bidirectional"))
    )
    (net (code "78") (name "B15_L16_P") (class "Default")
      (node (ref "JM2") (pin "25") (pinfunction "25_25") (pintype "bidirectional"))
    )
    (net (code "79") (name "B15_L17_N") (class "Default")
      (node (ref "JM2") (pin "31") (pinfunction "31_31") (pintype "bidirectional"))
    )
    (net (code "80") (name "B15_L17_P") (class "Default")
      (node (ref "JM2") (pin "33") (pinfunction "33_33") (pintype "bidirectional"))
    )
    (net (code "81") (name "B15_L18_N") (class "Default")
      (node (ref "JM2") (pin "27") (pinfunction "27_27") (pintype "bidirectional"))
      (node (ref "PCIE-SOUTH") (pin "A17") (pinfunction "LVDS_4B_A17") (pintype "passive"))
    )
    (net (code "82") (name "B15_L18_P") (class "Default")
      (node (ref "JM2") (pin "29") (pinfunction "29_29") (pintype "bidirectional"))
      (node (ref "PCIE-SOUTH") (pin "A16") (pinfunction "LVDS_4A_A16") (pintype "passive"))
    )
    (net (code "83") (name "B15_L19_N") (class "Default")
      (node (ref "JM2") (pin "41") (pinfunction "41_41") (pintype "bidirectional"))
      (node (ref "PCIE-SOUTH") (pin "B17") (pinfunction "LVDS_5B_B17") (pintype "passive"))
    )
    (net (code "84") (name "B15_L19_P") (class "Default")
      (node (ref "JM2") (pin "43") (pinfunction "43_43") (pintype "bidirectional"))
      (node (ref "PCIE-SOUTH") (pin "B16") (pinfunction "LVDS_5A_B16") (pintype "passive"))
    )
    (net (code "85") (name "B15_L20_N") (class "Default")
      (node (ref "JM2") (pin "50") (pinfunction "50_50") (pintype "bidirectional"))
    )
    (net (code "86") (name "B15_L20_P") (class "Default")
      (node (ref "JM2") (pin "52") (pinfunction "52_52") (pintype "bidirectional"))
    )
    (net (code "87") (name "B15_L21_N") (class "Default")
      (node (ref "JM2") (pin "45") (pinfunction "45_45") (pintype "bidirectional"))
    )
    (net (code "88") (name "B15_L21_P") (class "Default")
      (node (ref "JM2") (pin "47") (pinfunction "47_47") (pintype "bidirectional"))
    )
    (net (code "89") (name "B15_L22_N") (class "Default")
      (node (ref "JM2") (pin "46") (pinfunction "46_46") (pintype "bidirectional"))
      (node (ref "PCIE-SOUTH") (pin "A3") (pinfunction "LVDS_0B_A3") (pintype "passive"))
    )
    (net (code "90") (name "B15_L22_P") (class "Default")
      (node (ref "JM2") (pin "48") (pinfunction "48_48") (pintype "bidirectional"))
      (node (ref "PCIE-SOUTH") (pin "A2") (pinfunction "LVDS_0A_A2") (pintype "passive"))
    )
    (net (code "91") (name "B15_L23_N") (class "Default")
      (node (ref "JM2") (pin "51") (pinfunction "51_51") (pintype "bidirectional"))
      (node (ref "PCIE-SOUTH") (pin "A13") (pinfunction "LVDS_3A_A13") (pintype "passive"))
    )
    (net (code "92") (name "B15_L23_P") (class "Default")
      (node (ref "JM2") (pin "49") (pinfunction "49_49") (pintype "bidirectional"))
      (node (ref "PCIE-SOUTH") (pin "A14") (pinfunction "LVDS_3B_A14") (pintype "passive"))
    )
    (net (code "93") (name "B15_L24_N") (class "Default")
      (node (ref "JM2") (pin "37") (pinfunction "37_37") (pintype "bidirectional"))
    )
    (net (code "94") (name "B15_L24_P") (class "Default")
      (node (ref "JM2") (pin "39") (pinfunction "39_39") (pintype "bidirectional"))
    )
    (net (code "95") (name "B34_L1_N") (class "Default")
      (node (ref "JM1") (pin "37") (pinfunction "37_37") (pintype "bidirectional"))
    )
    (net (code "96") (name "B34_L1_P") (class "Default")
      (node (ref "JM1") (pin "35") (pinfunction "35_35") (pintype "bidirectional"))
    )
    (net (code "97") (name "B34_L2_N") (class "Default")
      (node (ref "JM1") (pin "33") (pinfunction "33_33") (pintype "bidirectional"))
    )
    (net (code "98") (name "B34_L2_P") (class "Default")
      (node (ref "JM1") (pin "31") (pinfunction "31_31") (pintype "bidirectional"))
    )
    (net (code "99") (name "B34_L3_N") (class "Default")
      (node (ref "JM1") (pin "42") (pinfunction "42_42") (pintype "bidirectional"))
      (node (ref "U3") (pin "13") (pinfunction "SCLK_13") (pintype "input"))
    )
    (net (code "100") (name "B34_L3_P") (class "Default")
      (node (ref "JM1") (pin "40") (pinfunction "40_40") (pintype "bidirectional"))
      (node (ref "U3") (pin "17") (pinfunction "GPIO0_17") (pintype "bidirectional"))
    )
    (net (code "101") (name "B34_L4_N") (class "Default")
      (node (ref "JM1") (pin "41") (pinfunction "41_41") (pintype "bidirectional"))
      (node (ref "U3") (pin "12") (pinfunction "SDOUT_12") (pintype "output"))
    )
    (net (code "102") (name "B34_L4_P") (class "Default")
      (node (ref "JM1") (pin "39") (pinfunction "39_39") (pintype "bidirectional"))
    )
    (net (code "103") (name "B34_L5_N") (class "Default")
      (node (ref "JM1") (pin "45") (pinfunction "45_45") (pintype "bidirectional"))
      (node (ref "U3") (pin "10") (pinfunction "~{CS}_10") (pintype "input"))
    )
    (net (code "104") (name "B34_L5_P") (class "Default")
      (node (ref "JM1") (pin "43") (pinfunction "43_43") (pintype "bidirectional"))
      (node (ref "U3") (pin "11") (pinfunction "SDIN_11") (pintype "input"))
    )
    (net (code "105") (name "B34_L6_N") (class "Default")
      (node (ref "JM1") (pin "34") (pinfunction "34_34") (pintype "bidirectional"))
    )
    (net (code "106") (name "B34_L6_P") (class "Default")
      (node (ref "JM1") (pin "32") (pinfunction "32_32") (pintype "bidirectional"))
    )
    (net (code "107") (name "B34_L7_N") (class "Default")
      (node (ref "JM1") (pin "38") (pinfunction "38_38") (pintype "bidirectional"))
      (node (ref "U3") (pin "18") (pinfunction "GPIO1_18") (pintype "bidirectional"))
    )
    (net (code "108") (name "B34_L7_P") (class "Default")
      (node (ref "JM1") (pin "36") (pinfunction "36_36") (pintype "bidirectional"))
    )
    (net (code "109") (name "B34_L8_N") (class "Default")
      (node (ref "JM1") (pin "52") (pinfunction "52_52") (pintype "bidirectional"))
      (node (ref "U2") (pin "13") (pinfunction "SCLK_13") (pintype "input"))
    )
    (net (code "110") (name "B34_L8_P") (class "Default")
      (node (ref "JM1") (pin "50") (pinfunction "50_50") (pintype "bidirectional"))
      (node (ref "U2") (pin "12") (pinfunction "SDOUT_12") (pintype "output"))
    )
    (net (code "111") (name "B34_L9_N") (class "Default")
      (node (ref "JM1") (pin "46") (pinfunction "46_46") (pintype "bidirectional"))
      (node (ref "U3") (pin "33") (pinfunction "GPIO2_33") (pintype "bidirectional"))
    )
    (net (code "112") (name "B34_L9_P") (class "Default")
      (node (ref "JM1") (pin "44") (pinfunction "44_44") (pintype "bidirectional"))
      (node (ref "U3") (pin "36") (pinfunction "GPIO3_36") (pintype "bidirectional"))
    )
    (net (code "113") (name "B34_L10_N") (class "Default")
      (node (ref "JM1") (pin "51") (pinfunction "51_51") (pintype "bidirectional"))
      (node (ref "U4") (pin "11") (pinfunction "SDIN_11") (pintype "input"))
    )
    (net (code "114") (name "B34_L10_P") (class "Default")
      (node (ref "JM1") (pin "49") (pinfunction "49_49") (pintype "bidirectional"))
      (node (ref "U4") (pin "10") (pinfunction "~{CS}_10") (pintype "input"))
    )
    (net (code "115") (name "B34_L11_N") (class "Default")
      (node (ref "JM1") (pin "53") (pinfunction "53_53") (pintype "bidirectional"))
      (node (ref "U4") (pin "12") (pinfunction "SDOUT_12") (pintype "output"))
    )
    (net (code "116") (name "B34_L11_P") (class "Default")
      (node (ref "JM1") (pin "55") (pinfunction "55_55") (pintype "bidirectional"))
      (node (ref "U4") (pin "18") (pinfunction "GPIO1_18") (pintype "bidirectional"))
    )
    (net (code "117") (name "B34_L12_N") (class "Default")
      (node (ref "JM1") (pin "57") (pinfunction "57_57") (pintype "bidirectional"))
      (node (ref "U4") (pin "17") (pinfunction "GPIO0_17") (pintype "bidirectional"))
    )
    (net (code "118") (name "B34_L12_P") (class "Default")
      (node (ref "JM1") (pin "59") (pinfunction "59_59") (pintype "bidirectional"))
      (node (ref "U2") (pin "11") (pinfunction "SDIN_11") (pintype "input"))
    )
    (net (code "119") (name "B34_L13_N") (class "Default")
      (node (ref "JM1") (pin "56") (pinfunction "56_56") (pintype "bidirectional"))
      (node (ref "U2") (pin "18") (pinfunction "GPIO1_18") (pintype "bidirectional"))
    )
    (net (code "120") (name "B34_L13_P") (class "Default")
      (node (ref "JM1") (pin "54") (pinfunction "54_54") (pintype "bidirectional"))
      (node (ref "U2") (pin "17") (pinfunction "GPIO0_17") (pintype "bidirectional"))
    )
    (net (code "121") (name "B34_L14_N") (class "Default")
      (node (ref "JM1") (pin "60") (pinfunction "60_60") (pintype "bidirectional"))
      (node (ref "U2") (pin "36") (pinfunction "GPIO3_36") (pintype "bidirectional"))
    )
    (net (code "122") (name "B34_L14_P") (class "Default")
      (node (ref "JM1") (pin "58") (pinfunction "58_58") (pintype "bidirectional"))
      (node (ref "U2") (pin "33") (pinfunction "GPIO2_33") (pintype "bidirectional"))
    )
    (net (code "123") (name "B34_L15_N") (class "Default")
      (node (ref "JM1") (pin "62") (pinfunction "62_62") (pintype "bidirectional"))
    )
    (net (code "124") (name "B34_L15_P") (class "Default")
      (node (ref "JM1") (pin "64") (pinfunction "64_64") (pintype "bidirectional"))
    )
    (net (code "125") (name "B34_L16_N") (class "Default")
      (node (ref "JM1") (pin "68") (pinfunction "68_68") (pintype "bidirectional"))
    )
    (net (code "126") (name "B34_L16_P") (class "Default")
      (node (ref "JM1") (pin "70") (pinfunction "70_70") (pintype "bidirectional"))
    )
    (net (code "127") (name "B34_L17_N") (class "Default")
      (node (ref "JM1") (pin "63") (pinfunction "63_63") (pintype "bidirectional"))
      (node (ref "U2") (pin "10") (pinfunction "~{CS}_10") (pintype "input"))
    )
    (net (code "128") (name "B34_L17_P") (class "Default")
      (node (ref "JM1") (pin "65") (pinfunction "65_65") (pintype "bidirectional"))
      (node (ref "U4") (pin "36") (pinfunction "GPIO3_36") (pintype "bidirectional"))
    )
    (net (code "129") (name "B34_L18_N") (class "Default")
      (node (ref "JM1") (pin "74") (pinfunction "74_74") (pintype "bidirectional"))
    )
    (net (code "130") (name "B34_L18_P") (class "Default")
      (node (ref "JM1") (pin "72") (pinfunction "72_72") (pintype "bidirectional"))
    )
    (net (code "131") (name "B34_L19_N") (class "Default")
      (node (ref "JM1") (pin "71") (pinfunction "71_71") (pintype "bidirectional"))
    )
    (net (code "132") (name "B34_L19_P") (class "Default")
      (node (ref "JM1") (pin "73") (pinfunction "73_73") (pintype "bidirectional"))
    )
    (net (code "133") (name "B34_L20_N") (class "Default")
      (node (ref "JM1") (pin "76") (pinfunction "76_76") (pintype "bidirectional"))
      (node (ref "R4") (pin "1") (pinfunction "1_1") (pintype "passive"))
    )
    (net (code "134") (name "B34_L20_P") (class "Default")
      (node (ref "JM1") (pin "78") (pinfunction "78_78") (pintype "bidirectional"))
      (node (ref "R5") (pin "1") (pinfunction "1_1") (pintype "passive"))
    )
    (net (code "135") (name "B34_L21_N") (class "Default")
      (node (ref "JM1") (pin "69") (pinfunction "69_69") (pintype "bidirectional"))
    )
    (net (code "136") (name "B34_L21_P") (class "Default")
      (node (ref "JM1") (pin "67") (pinfunction "67_67") (pintype "bidirectional"))
      (node (ref "U4") (pin "33") (pinfunction "GPIO2_33") (pintype "bidirectional"))
    )
    (net (code "137") (name "B34_L22_N") (class "Default")
      (node (ref "JM1") (pin "75") (pinfunction "75_75") (pintype "bidirectional"))
    )
    (net (code "138") (name "B34_L22_P") (class "Default")
      (node (ref "JM1") (pin "77") (pinfunction "77_77") (pintype "bidirectional"))
    )
    (net (code "139") (name "B34_L23_N") (class "Default")
      (node (ref "JM1") (pin "79") (pinfunction "79_79") (pintype "bidirectional"))
    )
    (net (code "140") (name "B34_L23_P") (class "Default")
      (node (ref "JM1") (pin "81") (pinfunction "81_81") (pintype "bidirectional"))
    )
    (net (code "141") (name "B34_L24_N") (class "Default")
      (node (ref "JM1") (pin "80") (pinfunction "80_80") (pintype "bidirectional"))
      (node (ref "R6") (pin "1") (pinfunction "1_1") (pintype "passive"))
    )
    (net (code "142") (name "B34_L24_P") (class "Default")
      (node (ref "JM1") (pin "82") (pinfunction "82_82") (pintype "bidirectional"))
      (node (ref "R7") (pin "1") (pinfunction "1_1") (pintype "passive"))
    )
    (net (code "143") (name "BOOTMODE") (class "Default")
      (node (ref "JM2") (pin "100") (pinfunction "100_100") (pintype "bidirectional"))
      (node (ref "JP3") (pin "1") (pinfunction "1_1") (pintype "passive"))
    )
    (net (code "144") (name "DONE") (class "Default")
      (node (ref "D5") (pin "A@1") (pinfunction "A_A@1") (pintype "passive"))
      (node (ref "JM1") (pin "96") (pinfunction "96_96") (pintype "bidirectional"))
      (node (ref "R3") (pin "1") (pinfunction "1_1") (pintype "passive"))
    )
    (net (code "145") (name "GND") (class "Default")
      (node (ref "C1") (pin "2") (pinfunction "2_2") (pintype "passive"))
      (node (ref "C10") (pin "2") (pinfunction "2_2") (pintype "passive"))
      (node (ref "C11") (pin "2") (pinfunction "2_2") (pintype "passive"))
      (node (ref "C12") (pin "2") (pinfunction "2_2") (pintype "passive"))
      (node (ref "C13") (pin "2") (pinfunction "2_2") (pintype "passive"))
      (node (ref "C14") (pin "2") (pinfunction "2_2") (pintype "passive"))
      (node (ref "C15") (pin "2") (pinfunction "2_2") (pintype "passive"))
      (node (ref "C16") (pin "2") (pinfunction "2_2") (pintype "passive"))
      (node (ref "C22") (pin "2") (pinfunction "2_2") (pintype "passive"))
      (node (ref "C23") (pin "2") (pinfunction "2_2") (pintype "passive"))
      (node (ref "C24") (pin "2") (pinfunction "2_2") (pintype "passive"))
      (node (ref "C25") (pin "2") (pinfunction "2_2") (pintype "passive"))
      (node (ref "C26") (pin "2") (pinfunction "2_2") (pintype "passive"))
      (node (ref "C27") (pin "2") (pinfunction "2_2") (pintype "passive"))
      (node (ref "C28") (pin "2") (pinfunction "2_2") (pintype "passive"))
      (node (ref "C29") (pin "2") (pinfunction "2_2") (pintype "passive"))
      (node (ref "C30") (pin "2") (pinfunction "2_2") (pintype "passive"))
      (node (ref "C31") (pin "2") (pinfunction "2_2") (pintype "passive"))
      (node (ref "C32") (pin "2") (pinfunction "2_2") (pintype "passive"))
      (node (ref "C33") (pin "2") (pinfunction "2_2") (pintype "passive"))
      (node (ref "C34") (pin "2") (pinfunction "2_2") (pintype "passive"))
      (node (ref "C40") (pin "2") (pinfunction "2_2") (pintype "passive"))
      (node (ref "C41") (pin "2") (pinfunction "2_2") (pintype "passive"))
      (node (ref "C42") (pin "2") (pinfunction "2_2") (pintype "passive"))
      (node (ref "C43") (pin "2") (pinfunction "2_2") (pintype "passive"))
      (node (ref "C44") (pin "2") (pinfunction "2_2") (pintype "passive"))
      (node (ref "C45") (pin "2") (pinfunction "2_2") (pintype "passive"))
      (node (ref "C46") (pin "2") (pinfunction "2_2") (pintype "passive"))
      (node (ref "C47") (pin "2") (pinfunction "2_2") (pintype "passive"))
      (node (ref "C48") (pin "2") (pinfunction "2_2") (pintype "passive"))
      (node (ref "C49") (pin "2") (pinfunction "2_2") (pintype "passive"))
      (node (ref "C5") (pin "2") (pinfunction "2_2") (pintype "passive"))
      (node (ref "C50") (pin "2") (pinfunction "2_2") (pintype "passive"))
      (node (ref "C51") (pin "2") (pinfunction "2_2") (pintype "passive"))
      (node (ref "C52") (pin "2") (pinfunction "2_2") (pintype "passive"))
      (node (ref "C53") (pin "2") (pinfunction "2_2") (pintype "passive"))
      (node (ref "C6") (pin "2") (pinfunction "2_2") (pintype "passive"))
      (node (ref "C7") (pin "2") (pinfunction "2_2") (pintype "passive"))
      (node (ref "C8") (pin "2") (pinfunction "2_2") (pintype "passive"))
      (node (ref "C9") (pin "2") (pinfunction "2_2") (pintype "passive"))
      (node (ref "D5") (pin "C@1") (pinfunction "C_C@1") (pintype "passive"))
      (node (ref "JM1") (pin "100") (pinfunction "100_100") (pintype "bidirectional"))
      (node (ref "JM1") (pin "11") (pinfunction "11_11") (pintype "bidirectional"))
      (node (ref "JM1") (pin "12") (pinfunction "12_12") (pintype "bidirectional"))
      (node (ref "JM1") (pin "17") (pinfunction "17_17") (pintype "bidirectional"))
      (node (ref "JM1") (pin "18") (pinfunction "18_18") (pintype "bidirectional"))
      (node (ref "JM1") (pin "23") (pinfunction "23_23") (pintype "bidirectional"))
      (node (ref "JM1") (pin "24") (pinfunction "24_24") (pintype "bidirectional"))
      (node (ref "JM1") (pin "29") (pinfunction "29_29") (pintype "bidirectional"))
      (node (ref "JM1") (pin "30") (pinfunction "30_30") (pintype "bidirectional"))
      (node (ref "JM1") (pin "47") (pinfunction "47_47") (pintype "bidirectional"))
      (node (ref "JM1") (pin "48") (pinfunction "48_48") (pintype "bidirectional"))
      (node (ref "JM1") (pin "5") (pinfunction "5_5") (pintype "bidirectional"))
      (node (ref "JM1") (pin "6") (pinfunction "6_6") (pintype "bidirectional"))
      (node (ref "JM1") (pin "66") (pinfunction "66_66") (pintype "bidirectional"))
      (node (ref "JM1") (pin "84") (pinfunction "84_84") (pintype "bidirectional"))
      (node (ref "JM1") (pin "98") (pinfunction "98_98") (pintype "bidirectional"))
      (node (ref "JM1") (pin "F1") (pinfunction "F1_F1") (pintype "bidirectional"))
      (node (ref "JM1") (pin "F2") (pinfunction "F2_F2") (pintype "bidirectional"))
      (node (ref "JM2") (pin "17") (pinfunction "17_17") (pintype "bidirectional"))
      (node (ref "JM2") (pin "35") (pinfunction "35_35") (pintype "bidirectional"))
      (node (ref "JM2") (pin "36") (pinfunction "36_36") (pintype "bidirectional"))
      (node (ref "JM2") (pin "72") (pinfunction "72_72") (pintype "bidirectional"))
      (node (ref "JM2") (pin "83") (pinfunction "83_83") (pintype "bidirectional"))
      (node (ref "JM2") (pin "90") (pinfunction "90_90") (pintype "bidirectional"))
      (node (ref "JM2") (pin "F1") (pinfunction "F1_F1") (pintype "bidirectional"))
      (node (ref "JM2") (pin "F2") (pinfunction "F2_F2") (pintype "bidirectional"))
      (node (ref "JP2") (pin "1") (pinfunction "1_1") (pintype "passive"))
      (node (ref "JP3") (pin "2") (pinfunction "2_2") (pintype "passive"))
      (node (ref "PCIE-NORTH") (pin "A1") (pinfunction "GND_A1") (pintype "passive"))
      (node (ref "PCIE-NORTH") (pin "A10") (pinfunction "GND_A10") (pintype "passive"))
      (node (ref "PCIE-NORTH") (pin "A12") (pinfunction "GND_A12") (pintype "passive"))
      (node (ref "PCIE-NORTH") (pin "A15") (pinfunction "GND_A15") (pintype "passive"))
      (node (ref "PCIE-NORTH") (pin "A18") (pinfunction "GND_A18") (pintype "passive"))
      (node (ref "PCIE-NORTH") (pin "A4") (pinfunction "GND_A4") (pintype "passive"))
      (node (ref "PCIE-NORTH") (pin "A7") (pinfunction "GND_A7") (pintype "passive"))
      (node (ref "PCIE-NORTH") (pin "B15") (pinfunction "GND_B15") (pintype "passive"))
      (node (ref "PCIE-NORTH") (pin "B18") (pinfunction "GND_B18") (pintype "passive"))
      (node (ref "PCIE-SOUTH") (pin "A1") (pinfunction "GND_A1") (pintype "passive"))
      (node (ref "PCIE-SOUTH") (pin "A10") (pinfunction "GND_A10") (pintype "passive"))
      (node (ref "PCIE-SOUTH") (pin "A12") (pinfunction "GND_A12") (pintype "passive"))
      (node (ref "PCIE-SOUTH") (pin "A15") (pinfunction "GND_A15") (pintype "passive"))
      (node (ref "PCIE-SOUTH") (pin "A18") (pinfunction "GND_A18") (pintype "passive"))
      (node (ref "PCIE-SOUTH") (pin "A4") (pinfunction "GND_A4") (pintype "passive"))
      (node (ref "PCIE-SOUTH") (pin "A7") (pinfunction "GND_A7") (pintype "passive"))
      (node (ref "PCIE-SOUTH") (pin "B15") (pinfunction "GND_B15") (pintype "passive"))
      (node (ref "PCIE-SOUTH") (pin "B18") (pinfunction "GND_B18") (pintype "passive"))
      (node (ref "R10") (pin "2") (pinfunction "2_2") (pintype "passive"))
      (node (ref "R11") (pin "2") (pinfunction "2_2") (pintype "passive"))
      (node (ref "R12") (pin "2") (pinfunction "2_2") (pintype "passive"))
      (node (ref "R13") (pin "2") (pinfunction "2_2") (pintype "passive"))
      (node (ref "R14") (pin "2") (pinfunction "2_2") (pintype "passive"))
      (node (ref "R2") (pin "2") (pinfunction "2_2") (pintype "passive"))
      (node (ref "R8") (pin "2") (pinfunction "2_2") (pintype "passive"))
      (node (ref "R9") (pin "2") (pinfunction "2_2") (pintype "passive"))
      (node (ref "U1") (pin "1") (pinfunction "A0_1") (pintype "input"))
      (node (ref "U1") (pin "2") (pinfunction "A1_2") (pintype "input"))
      (node (ref "U1") (pin "3") (pinfunction "A2_3") (pintype "input"))
      (node (ref "U1") (pin "4") (pinfunction "GND_4") (pintype "passive"))
      (node (ref "U1") (pin "EP") (pinfunction "EP_EP") (pintype "passive"))
      (node (ref "U2") (pin "1") (pinfunction "VEE_SDI_1") (pintype "power_in"))
      (node (ref "U2") (pin "14") (pinfunction "VSS_14") (pintype "power_in"))
      (node (ref "U2") (pin "15") (pinfunction "VSS_15") (pintype "power_in"))
      (node (ref "U2") (pin "19") (pinfunction "VEE_CORE_19") (pintype "power_in"))
      (node (ref "U2") (pin "21") (pinfunction "VEEO_21") (pintype "power_in"))
      (node (ref "U2") (pin "28") (pinfunction "VEEO_28") (pintype "power_in"))
      (node (ref "U2") (pin "31") (pinfunction "VEE_CORE_31") (pintype "power_in"))
      (node (ref "U2") (pin "37") (pinfunction "VEE_CORE_37") (pintype "power_in"))
      (node (ref "U2") (pin "38") (pinfunction "VEE_CORE_38") (pintype "power_in"))
      (node (ref "U2") (pin "8") (pinfunction "VEE_SDI_8") (pintype "power_in"))
      (node (ref "U3") (pin "1") (pinfunction "VEE_DDI_1") (pintype "power_in"))
      (node (ref "U3") (pin "14") (pinfunction "VSS_14") (pintype "power_in"))
      (node (ref "U3") (pin "15") (pinfunction "VSS_15") (pintype "power_in"))
      (node (ref "U3") (pin "19") (pinfunction "VEE_CORE_19") (pintype "power_in"))
      (node (ref "U3") (pin "21") (pinfunction "VEEO_21") (pintype "power_in"))
      (node (ref "U3") (pin "28") (pinfunction "VEEO_28") (pintype "power_in"))
      (node (ref "U3") (pin "31") (pinfunction "VEE_CORE_31") (pintype "power_in"))
      (node (ref "U3") (pin "37") (pinfunction "VEE_CORE_37") (pintype "power_in"))
      (node (ref "U3") (pin "38") (pinfunction "VEE_CORE_38") (pintype "power_in"))
      (node (ref "U3") (pin "8") (pinfunction "VEE_DDI_8") (pintype "power_in"))
      (node (ref "U4") (pin "1") (pinfunction "VEE_DDI_1") (pintype "power_in"))
      (node (ref "U4") (pin "14") (pinfunction "VSS_14") (pintype "power_in"))
      (node (ref "U4") (pin "15") (pinfunction "VSS_15") (pintype "power_in"))
      (node (ref "U4") (pin "19") (pinfunction "VEE_CORE_19") (pintype "power_in"))
      (node (ref "U4") (pin "21") (pinfunction "VEEO_21") (pintype "power_in"))
      (node (ref "U4") (pin "28") (pinfunction "VEEO_28") (pintype "power_in"))
      (node (ref "U4") (pin "31") (pinfunction "VEE_CORE_31") (pintype "power_in"))
      (node (ref "U4") (pin "37") (pinfunction "VEE_CORE_37") (pintype "power_in"))
      (node (ref "U4") (pin "38") (pinfunction "VEE_CORE_38") (pintype "power_in"))
      (node (ref "U4") (pin "8") (pinfunction "VEE_DDI_8") (pintype "power_in"))
      (node (ref "U5") (pin "3") (pinfunction "GND_3") (pintype "passive"))
      (node (ref "X1") (pin "2@1") (pinfunction "GND_2@1") (pintype "passive"))
      (node (ref "X1") (pin "2@2") (pinfunction "GND_2@2") (pintype "passive"))
      (node (ref "X1") (pin "2@3") (pinfunction "GND_2@3") (pintype "passive"))
      (node (ref "X2") (pin "2@1") (pinfunction "GND_2@1") (pintype "passive"))
      (node (ref "X2") (pin "2@2") (pinfunction "GND_2@2") (pintype "passive"))
      (node (ref "X2") (pin "2@3") (pinfunction "GND_2@3") (pintype "passive"))
      (node (ref "X3") (pin "2@1") (pinfunction "GND_2@1") (pintype "passive"))
      (node (ref "X3") (pin "2@2") (pinfunction "GND_2@2") (pintype "passive"))
      (node (ref "X3") (pin "2@3") (pinfunction "GND_2@3") (pintype "passive"))
    )
    (net (code "146") (name "I2C_V") (class "Default")
      (node (ref "C1") (pin "1") (pinfunction "1_1") (pintype "passive"))
      (node (ref "PCIE-NORTH") (pin "B3") (pinfunction "V_I2C_B3") (pintype "passive"))
      (node (ref "R1") (pin "1") (pinfunction "1_1") (pintype "passive"))
      (node (ref "U1") (pin "8") (pinfunction "VCC_8") (pintype "power_in"))
    )
    (net (code "147") (name "MGT_CLK0_N") (class "Default")
      (node (ref "C55") (pin "2") (pinfunction "2_2") (pintype "passive"))
      (node (ref "JM1") (pin "4") (pinfunction "4_4") (pintype "bidirectional"))
    )
    (net (code "148") (name "MGT_CLK0_P") (class "Default")
      (node (ref "C54") (pin "2") (pinfunction "2_2") (pintype "passive"))
      (node (ref "JM1") (pin "2") (pinfunction "2_2") (pintype "bidirectional"))
    )
    (net (code "149") (name "MGT_RX0_N") (class "Default")
      (node (ref "JM1") (pin "21") (pinfunction "21_21") (pintype "bidirectional"))
      (node (ref "U2") (pin "27") (pinfunction "DDO0_27") (pintype "output"))
    )
    (net (code "150") (name "MGT_RX0_P") (class "Default")
      (node (ref "JM1") (pin "19") (pinfunction "19_19") (pintype "bidirectional"))
      (node (ref "U2") (pin "26") (pinfunction "~{DDO0}_26") (pintype "output"))
    )
    (net (code "151") (name "MGT_RX1_N") (class "Default")
      (node (ref "JM1") (pin "15") (pinfunction "15_15") (pintype "bidirectional"))
      (node (ref "U2") (pin "23") (pinfunction "DDO1/RCO_23") (pintype "output"))
    )
    (net (code "152") (name "MGT_RX1_P") (class "Default")
      (node (ref "JM1") (pin "13") (pinfunction "13_13") (pintype "bidirectional"))
      (node (ref "U2") (pin "22") (pinfunction "~{DDO1}/~{RCO}_22") (pintype "output"))
    )
    (net (code "153") (name "MGT_RX2_N") (class "Default")
      (node (ref "JM1") (pin "9") (pinfunction "9_9") (pintype "bidirectional"))
    )
    (net (code "154") (name "MGT_RX2_P") (class "Default")
      (node (ref "JM1") (pin "7") (pinfunction "7_7") (pintype "bidirectional"))
    )
    (net (code "155") (name "MGT_RX3_N") (class "Default")
      (node (ref "JM1") (pin "3") (pinfunction "3_3") (pintype "bidirectional"))
    )
    (net (code "156") (name "MGT_RX3_P") (class "Default")
      (node (ref "JM1") (pin "1") (pinfunction "1_1") (pintype "bidirectional"))
    )
    (net (code "157") (name "MGT_TX0_N") (class "Default")
      (node (ref "JM1") (pin "28") (pinfunction "28_28") (pintype "bidirectional"))
      (node (ref "U4") (pin "6") (pinfunction "DDI_6") (pintype "input"))
    )
    (net (code "158") (name "MGT_TX0_P") (class "Default")
      (node (ref "JM1") (pin "26") (pinfunction "26_26") (pintype "bidirectional"))
      (node (ref "U4") (pin "7") (pinfunction "~{DDI}_7") (pintype "input"))
    )
    (net (code "159") (name "MGT_TX1_N") (class "Default")
      (node (ref "JM1") (pin "22") (pinfunction "22_22") (pintype "bidirectional"))
      (node (ref "U3") (pin "6") (pinfunction "DDI_6") (pintype "input"))
    )
    (net (code "160") (name "MGT_TX1_P") (class "Default")
      (node (ref "JM1") (pin "20") (pinfunction "20_20") (pintype "bidirectional"))
      (node (ref "U3") (pin "7") (pinfunction "~{DDI}_7") (pintype "input"))
    )
    (net (code "161") (name "MGT_TX2_N") (class "Default")
      (node (ref "JM1") (pin "16") (pinfunction "16_16") (pintype "bidirectional"))
    )
    (net (code "162") (name "MGT_TX2_P") (class "Default")
      (node (ref "JM1") (pin "14") (pinfunction "14_14") (pintype "bidirectional"))
    )
    (net (code "163") (name "MGT_TX3_N") (class "Default")
      (node (ref "JM1") (pin "10") (pinfunction "10_10") (pintype "bidirectional"))
    )
    (net (code "164") (name "MGT_TX3_P") (class "Default")
      (node (ref "JM1") (pin "8") (pinfunction "8_8") (pintype "bidirectional"))
    )
    (net (code "165") (name "N$34") (class "Default")
      (node (ref "U3") (pin "32") (pinfunction "RCLK_32") (pintype "input"))
    )
    (net (code "166") (name "N$81") (class "Default")
      (node (ref "U4") (pin "32") (pinfunction "RCLK_32") (pintype "input"))
    )
    (net (code "167") (name "N$83") (class "Default")
      (node (ref "U4") (pin "13") (pinfunction "SCLK_13") (pintype "input"))
    )
    (net (code "168") (name "N_5V") (class "Default")
      (node (ref "PCIE-NORTH") (pin "B12") (pinfunction "5V_B12") (pintype "passive"))
    )
    (net (code "169") (name "N_IO0") (class "Default")
      (node (ref "PCIE-NORTH") (pin "B4") (pinfunction "IO0_B4") (pintype "passive"))
    )
    (net (code "170") (name "N_IO1") (class "Default")
      (node (ref "PCIE-NORTH") (pin "B5") (pinfunction "IO1_B5") (pintype "passive"))
    )
    (net (code "171") (name "N_IO2") (class "Default")
      (node (ref "PCIE-NORTH") (pin "B6") (pinfunction "IO2_B6") (pintype "passive"))
    )
    (net (code "172") (name "N_IO3") (class "Default")
      (node (ref "PCIE-NORTH") (pin "B7") (pinfunction "IO3_B7") (pintype "passive"))
    )
    (net (code "173") (name "N_IO4") (class "Default")
      (node (ref "PCIE-NORTH") (pin "B8") (pinfunction "IO4_B8") (pintype "passive"))
    )
    (net (code "174") (name "N_IO5") (class "Default")
      (node (ref "PCIE-NORTH") (pin "B9") (pinfunction "IO5_B9") (pintype "passive"))
    )
    (net (code "175") (name "N_IO6") (class "Default")
      (node (ref "PCIE-NORTH") (pin "B10") (pinfunction "IO6_B10") (pintype "passive"))
    )
    (net (code "176") (name "N_IO7") (class "Default")
      (node (ref "PCIE-NORTH") (pin "B11") (pinfunction "IO7_B11") (pintype "passive"))
    )
    (net (code "177") (name "N_PCIE_V") (class "Default")
      (node (ref "PCIE-NORTH") (pin "B13") (pinfunction "VCC_B13") (pintype "passive"))
    )
    (net (code "178") (name "N_VCCIO") (class "Default")
      (node (ref "PCIE-NORTH") (pin "B14") (pinfunction "VCCIO_B14") (pintype "passive"))
    )
    (net (code "179") (name "Net-(C2-Pad1)") (class "Default")
      (node (ref "C2") (pin "1") (pinfunction "1_1") (pintype "passive"))
      (node (ref "X1") (pin "1") (pinfunction "1_1") (pintype "passive"))
    )
    (net (code "180") (name "Net-(C4-Pad2)") (class "Default")
      (node (ref "C4") (pin "2") (pinfunction "2_2") (pintype "passive"))
      (node (ref "R8") (pin "1") (pinfunction "1_1") (pintype "passive"))
    )
    (net (code "181") (name "Net-(C17-Pad2)") (class "Default")
      (node (ref "C17") (pin "2") (pinfunction "2_2") (pintype "passive"))
      (node (ref "X2") (pin "1") (pinfunction "1_1") (pintype "passive"))
    )
    (net (code "182") (name "Net-(C18-Pad2)") (class "Default")
      (node (ref "C18") (pin "2") (pinfunction "2_2") (pintype "passive"))
      (node (ref "R9") (pin "1") (pinfunction "1_1") (pintype "passive"))
    )
    (net (code "183") (name "Net-(C19-Pad2)") (class "Default")
      (node (ref "C19") (pin "2") (pinfunction "2_2") (pintype "passive"))
      (node (ref "R10") (pin "1") (pinfunction "1_1") (pintype "passive"))
    )
    (net (code "184") (name "Net-(C20-Pad2)") (class "Default")
      (node (ref "C20") (pin "2") (pinfunction "2_2") (pintype "passive"))
      (node (ref "R11") (pin "1") (pinfunction "1_1") (pintype "passive"))
    )
    (net (code "185") (name "Net-(C35-Pad2)") (class "Default")
      (node (ref "C35") (pin "2") (pinfunction "2_2") (pintype "passive"))
      (node (ref "X3") (pin "1") (pinfunction "1_1") (pintype "passive"))
    )
    (net (code "186") (name "Net-(C36-Pad2)") (class "Default")
      (node (ref "C36") (pin "2") (pinfunction "2_2") (pintype "passive"))
      (node (ref "R12") (pin "1") (pinfunction "1_1") (pintype "passive"))
    )
    (net (code "187") (name "Net-(C37-Pad2)") (class "Default")
      (node (ref "C37") (pin "2") (pinfunction "2_2") (pintype "passive"))
      (node (ref "R13") (pin "1") (pinfunction "1_1") (pintype "passive"))
    )
    (net (code "188") (name "Net-(C38-Pad2)") (class "Default")
      (node (ref "C38") (pin "2") (pinfunction "2_2") (pintype "passive"))
      (node (ref "R14") (pin "1") (pinfunction "1_1") (pintype "passive"))
    )
    (net (code "189") (name "Net-(D1-C)") (class "Default")
      (node (ref "D1") (pin "C@1") (pinfunction "C_C@1") (pintype "passive"))
      (node (ref "R4") (pin "2") (pinfunction "2_2") (pintype "passive"))
    )
    (net (code "190") (name "Net-(D2-C)") (class "Default")
      (node (ref "D2") (pin "C@1") (pinfunction "C_C@1") (pintype "passive"))
      (node (ref "R5") (pin "2") (pinfunction "2_2") (pintype "passive"))
    )
    (net (code "191") (name "Net-(D3-C)") (class "Default")
      (node (ref "D3") (pin "C@1") (pinfunction "C_C@1") (pintype "passive"))
      (node (ref "R6") (pin "2") (pinfunction "2_2") (pintype "passive"))
    )
    (net (code "192") (name "Net-(D4-C)") (class "Default")
      (node (ref "D4") (pin "C@1") (pinfunction "C_C@1") (pintype "passive"))
      (node (ref "R7") (pin "2") (pinfunction "2_2") (pintype "passive"))
    )
    (net (code "193") (name "Net-(U1-WP)") (class "Default")
      (node (ref "R1") (pin "2") (pinfunction "2_2") (pintype "passive"))
      (node (ref "R2") (pin "1") (pinfunction "1_1") (pintype "passive"))
      (node (ref "U1") (pin "7") (pinfunction "WP_7") (pintype "input"))
    )
    (net (code "194") (name "Net-(U2-LF+)") (class "Default")
      (node (ref "C3") (pin "1") (pinfunction "1_1") (pintype "passive"))
      (node (ref "U2") (pin "39") (pinfunction "LF+_39") (pintype "passive"))
    )
    (net (code "195") (name "Net-(U2-LF-)") (class "Default")
      (node (ref "C3") (pin "2") (pinfunction "2_2") (pintype "passive"))
      (node (ref "U2") (pin "40") (pinfunction "LF-_40") (pintype "passive"))
    )
    (net (code "196") (name "Net-(U2-SDI)") (class "Default")
      (node (ref "C2") (pin "2") (pinfunction "2_2") (pintype "passive"))
      (node (ref "U2") (pin "2") (pinfunction "SDI_2") (pintype "input"))
    )
    (net (code "197") (name "Net-(U2-SDI_TERM)") (class "Default")
      (node (ref "C4") (pin "1") (pinfunction "1_1") (pintype "passive"))
      (node (ref "U2") (pin "3") (pinfunction "SDI_TERM_3") (pintype "passive"))
    )
    (net (code "198") (name "Net-(U2-VCO_FILT)") (class "Default")
      (node (ref "C5") (pin "1") (pinfunction "1_1") (pintype "passive"))
      (node (ref "U2") (pin "34") (pinfunction "VCO_FILT_34") (pintype "passive"))
    )
    (net (code "199") (name "Net-(U2-VCO_FILT10)") (class "Default")
      (node (ref "C6") (pin "1") (pinfunction "1_1") (pintype "passive"))
      (node (ref "U2") (pin "30") (pinfunction "VCO_FILT10_30") (pintype "passive"))
    )
    (net (code "200") (name "Net-(U3-LF+)") (class "Default")
      (node (ref "C21") (pin "1") (pinfunction "1_1") (pintype "passive"))
      (node (ref "U3") (pin "39") (pinfunction "LF+_39") (pintype "passive"))
    )
    (net (code "201") (name "Net-(U3-LF-)") (class "Default")
      (node (ref "C21") (pin "2") (pinfunction "2_2") (pintype "passive"))
      (node (ref "U3") (pin "40") (pinfunction "LF-_40") (pintype "passive"))
    )
    (net (code "202") (name "Net-(U3-SDO0)") (class "Default")
      (node (ref "C17") (pin "1") (pinfunction "1_1") (pintype "passive"))
      (node (ref "U3") (pin "27") (pinfunction "SDO0_27") (pintype "output"))
    )
    (net (code "203") (name "Net-(U3-SDO1{slash}RCO)") (class "Default")
      (node (ref "C19") (pin "1") (pinfunction "1_1") (pintype "passive"))
      (node (ref "U3") (pin "23") (pinfunction "SDO1/RCO_23") (pintype "output"))
    )
    (net (code "204") (name "Net-(U3-TERM)") (class "Default")
      (node (ref "C22") (pin "1") (pinfunction "1_1") (pintype "passive"))
      (node (ref "U3") (pin "5") (pinfunction "TERM_5") (pintype "passive"))
    )
    (net (code "205") (name "Net-(U3-VCO_FILT)") (class "Default")
      (node (ref "C23") (pin "1") (pinfunction "1_1") (pintype "passive"))
      (node (ref "U3") (pin "34") (pinfunction "VCO_FILT_34") (pintype "passive"))
    )
    (net (code "206") (name "Net-(U3-VCO_FILT10)") (class "Default")
      (node (ref "C24") (pin "1") (pinfunction "1_1") (pintype "passive"))
      (node (ref "U3") (pin "30") (pinfunction "VCO_FILT10_30") (pintype "passive"))
    )
    (net (code "207") (name "Net-(U3-~{SDO0})") (class "Default")
      (node (ref "C20") (pin "1") (pinfunction "1_1") (pintype "passive"))
      (node (ref "U3") (pin "26") (pinfunction "~{SDO0}_26") (pintype "output"))
    )
    (net (code "208") (name "Net-(U3-~{SDO1}{slash}~{RCO})") (class "Default")
      (node (ref "C18") (pin "1") (pinfunction "1_1") (pintype "passive"))
      (node (ref "U3") (pin "22") (pinfunction "~{SDO1}/~{RCO}_22") (pintype "output"))
    )
    (net (code "209") (name "Net-(U4-LF+)") (class "Default")
      (node (ref "C39") (pin "1") (pinfunction "1_1") (pintype "passive"))
      (node (ref "U4") (pin "39") (pinfunction "LF+_39") (pintype "passive"))
    )
    (net (code "210") (name "Net-(U4-LF-)") (class "Default")
      (node (ref "C39") (pin "2") (pinfunction "2_2") (pintype "passive"))
      (node (ref "U4") (pin "40") (pinfunction "LF-_40") (pintype "passive"))
    )
    (net (code "211") (name "Net-(U4-SDO0)") (class "Default")
      (node (ref "C37") (pin "1") (pinfunction "1_1") (pintype "passive"))
      (node (ref "U4") (pin "27") (pinfunction "SDO0_27") (pintype "output"))
    )
    (net (code "212") (name "Net-(U4-SDO1{slash}RCO)") (class "Default")
      (node (ref "C35") (pin "1") (pinfunction "1_1") (pintype "passive"))
      (node (ref "U4") (pin "23") (pinfunction "SDO1/RCO_23") (pintype "output"))
    )
    (net (code "213") (name "Net-(U4-TERM)") (class "Default")
      (node (ref "C40") (pin "1") (pinfunction "1_1") (pintype "passive"))
      (node (ref "U4") (pin "5") (pinfunction "TERM_5") (pintype "passive"))
    )
    (net (code "214") (name "Net-(U4-VCO_FILT)") (class "Default")
      (node (ref "C41") (pin "1") (pinfunction "1_1") (pintype "passive"))
      (node (ref "U4") (pin "34") (pinfunction "VCO_FILT_34") (pintype "passive"))
    )
    (net (code "215") (name "Net-(U4-VCO_FILT10)") (class "Default")
      (node (ref "C42") (pin "1") (pinfunction "1_1") (pintype "passive"))
      (node (ref "U4") (pin "30") (pinfunction "VCO_FILT10_30") (pintype "passive"))
    )
    (net (code "216") (name "Net-(U4-~{SDO0})") (class "Default")
      (node (ref "C38") (pin "1") (pinfunction "1_1") (pintype "passive"))
      (node (ref "U4") (pin "26") (pinfunction "~{SDO0}_26") (pintype "output"))
    )
    (net (code "217") (name "Net-(U4-~{SDO1}{slash}~{RCO})") (class "Default")
      (node (ref "C36") (pin "1") (pinfunction "1_1") (pintype "passive"))
      (node (ref "U4") (pin "22") (pinfunction "~{SDO1}/~{RCO}_22") (pintype "output"))
    )
    (net (code "218") (name "Net-(U5-OUT+)") (class "Default")
      (node (ref "C54") (pin "1") (pinfunction "1_1") (pintype "passive"))
      (node (ref "R15") (pin "1") (pinfunction "1_1") (pintype "passive"))
      (node (ref "U5") (pin "4") (pinfunction "OUT+_4") (pintype "output"))
    )
    (net (code "219") (name "Net-(U5-OUT-)") (class "Default")
      (node (ref "C55") (pin "1") (pinfunction "1_1") (pintype "passive"))
      (node (ref "R15") (pin "2") (pinfunction "2_2") (pintype "passive"))
      (node (ref "U5") (pin "5") (pinfunction "OUT-_5") (pintype "output"))
    )
    (net (code "220") (name "PROG_B") (class "Default")
      (node (ref "JM1") (pin "94") (pinfunction "94_94") (pintype "bidirectional"))
    )
    (net (code "221") (name "SCL") (class "Default")
      (node (ref "PCIE-NORTH") (pin "B2") (pinfunction "SCL_B2") (pintype "passive"))
      (node (ref "U1") (pin "6") (pinfunction "SCL_6") (pintype "input"))
    )
    (net (code "222") (name "SDA") (class "Default")
      (node (ref "PCIE-NORTH") (pin "B1") (pinfunction "SDA_B1") (pintype "passive"))
      (node (ref "U1") (pin "5") (pinfunction "SDA_5") (pintype "bidirectional"))
    )
    (net (code "223") (name "SPI-CLK") (class "Default")
      (node (ref "JM2") (pin "67") (pinfunction "67_67") (pintype "bidirectional"))
    )
    (net (code "224") (name "SPI-CS") (class "Default")
      (node (ref "JM2") (pin "69") (pinfunction "69_69") (pintype "bidirectional"))
    )
    (net (code "225") (name "SPI-DQ0") (class "Default")
      (node (ref "JM2") (pin "68") (pinfunction "68_68") (pintype "bidirectional"))
    )
    (net (code "226") (name "SPI-DQ1") (class "Default")
      (node (ref "JM2") (pin "71") (pinfunction "71_71") (pintype "bidirectional"))
    )
    (net (code "227") (name "SPI-DQ2") (class "Default")
      (node (ref "JM2") (pin "73") (pinfunction "73_73") (pintype "bidirectional"))
    )
    (net (code "228") (name "SPI-DQ3") (class "Default")
      (node (ref "JM2") (pin "70") (pinfunction "70_70") (pintype "bidirectional"))
    )
    (net (code "229") (name "S_5V") (class "Default")
      (node (ref "PCIE-SOUTH") (pin "B12") (pinfunction "5V_B12") (pintype "passive"))
    )
    (net (code "230") (name "S_PCIE_V") (class "Default")
      (node (ref "PCIE-SOUTH") (pin "B13") (pinfunction "VCC_B13") (pintype "passive"))
    )
    (net (code "231") (name "S_VCCIO") (class "Default")
      (node (ref "PCIE-SOUTH") (pin "B14") (pinfunction "VCCIO_B14") (pintype "passive"))
    )
    (net (code "232") (name "TCK") (class "Default")
      (node (ref "JM1") (pin "90") (pinfunction "90_90") (pintype "bidirectional"))
    )
    (net (code "233") (name "TDI") (class "Default")
      (node (ref "JM1") (pin "86") (pinfunction "86_86") (pintype "bidirectional"))
    )
    (net (code "234") (name "TDO") (class "Default")
      (node (ref "JM1") (pin "88") (pinfunction "88_88") (pintype "bidirectional"))
    )
    (net (code "235") (name "TMS") (class "Default")
      (node (ref "JM1") (pin "92") (pinfunction "92_92") (pintype "bidirectional"))
    )
    (net (code "236") (name "VCCIO0") (class "Default")
      (node (ref "JM2") (pin "53") (pinfunction "53_53") (pintype "bidirectional"))
    )
    (net (code "237") (name "VCCIO15") (class "Default")
      (node (ref "JM2") (pin "54") (pinfunction "54_54") (pintype "bidirectional"))
    )
    (net (code "238") (name "VCCIO34") (class "Default")
      (node (ref "JM1") (pin "61") (pinfunction "61_61") (pintype "bidirectional"))
    )
    (net (code "239") (name "VCCO_4") (class "Default")
      (node (ref "C14") (pin "1") (pinfunction "1_1") (pintype "passive"))
      (node (ref "C15") (pin "1") (pinfunction "1_1") (pintype "passive"))
      (node (ref "C16") (pin "1") (pinfunction "1_1") (pintype "passive"))
      (node (ref "FB3") (pin "2") (pinfunction "2_2") (pintype "passive"))
      (node (ref "U2") (pin "24") (pinfunction "VCCO_1_24") (pintype "power_in"))
      (node (ref "U2") (pin "25") (pinfunction "VCCO_0_25") (pintype "power_in"))
    )
    (net (code "240") (name "VCCO_8") (class "Default")
      (node (ref "C32") (pin "1") (pinfunction "1_1") (pintype "passive"))
      (node (ref "C33") (pin "1") (pinfunction "1_1") (pintype "passive"))
      (node (ref "C34") (pin "1") (pinfunction "1_1") (pintype "passive"))
      (node (ref "FB6") (pin "2") (pinfunction "2_2") (pintype "passive"))
      (node (ref "U3") (pin "24") (pinfunction "VCCO_1_24") (pintype "power_in"))
      (node (ref "U3") (pin "25") (pinfunction "VCCO_0_25") (pintype "power_in"))
    )
    (net (code "241") (name "VCCO_9") (class "Default")
      (node (ref "C50") (pin "1") (pinfunction "1_1") (pintype "passive"))
      (node (ref "C51") (pin "1") (pinfunction "1_1") (pintype "passive"))
      (node (ref "C52") (pin "1") (pinfunction "1_1") (pintype "passive"))
      (node (ref "FB9") (pin "2") (pinfunction "2_2") (pintype "passive"))
      (node (ref "U4") (pin "24") (pinfunction "VCCO_1_24") (pintype "power_in"))
      (node (ref "U4") (pin "25") (pinfunction "VCCO_0_25") (pintype "power_in"))
    )
    (net (code "242") (name "VCC_4") (class "Default")
      (node (ref "C11") (pin "1") (pinfunction "1_1") (pintype "passive"))
      (node (ref "C12") (pin "1") (pinfunction "1_1") (pintype "passive"))
      (node (ref "C13") (pin "1") (pinfunction "1_1") (pintype "passive"))
      (node (ref "FB2") (pin "2") (pinfunction "2_2") (pintype "passive"))
      (node (ref "U2") (pin "35") (pinfunction "VCC_CORE_35") (pintype "power_in"))
      (node (ref "U2") (pin "4") (pinfunction "VCC_SDI_4") (pintype "power_in"))
    )
    (net (code "243") (name "VCC_8") (class "Default")
      (node (ref "C29") (pin "1") (pinfunction "1_1") (pintype "passive"))
      (node (ref "C30") (pin "1") (pinfunction "1_1") (pintype "passive"))
      (node (ref "C31") (pin "1") (pinfunction "1_1") (pintype "passive"))
      (node (ref "FB5") (pin "2") (pinfunction "2_2") (pintype "passive"))
      (node (ref "U3") (pin "35") (pinfunction "VCC_CORE_35") (pintype "power_in"))
      (node (ref "U3") (pin "4") (pinfunction "VCC_DDI_4") (pintype "power_in"))
    )
    (net (code "244") (name "VCC_9") (class "Default")
      (node (ref "C47") (pin "1") (pinfunction "1_1") (pintype "passive"))
      (node (ref "C48") (pin "1") (pinfunction "1_1") (pintype "passive"))
      (node (ref "C49") (pin "1") (pinfunction "1_1") (pintype "passive"))
      (node (ref "FB8") (pin "2") (pinfunction "2_2") (pintype "passive"))
      (node (ref "U4") (pin "35") (pinfunction "VCC_CORE_35") (pintype "power_in"))
      (node (ref "U4") (pin "4") (pinfunction "VCC_DDI_4") (pintype "power_in"))
    )
    (net (code "245") (name "VDD_4") (class "Default")
      (node (ref "C10") (pin "1") (pinfunction "1_1") (pintype "passive"))
      (node (ref "C7") (pin "1") (pinfunction "1_1") (pintype "passive"))
      (node (ref "C8") (pin "1") (pinfunction "1_1") (pintype "passive"))
      (node (ref "C9") (pin "1") (pinfunction "1_1") (pintype "passive"))
      (node (ref "FB1") (pin "2") (pinfunction "2_2") (pintype "passive"))
      (node (ref "U2") (pin "16") (pinfunction "VDD_16") (pintype "power_in"))
      (node (ref "U2") (pin "20") (pinfunction "VCCO1V8_1_20") (pintype "power_in"))
      (node (ref "U2") (pin "29") (pinfunction "VCCO1V8_0_29") (pintype "power_in"))
    )
    (net (code "246") (name "VDD_8") (class "Default")
      (node (ref "C25") (pin "1") (pinfunction "1_1") (pintype "passive"))
      (node (ref "C26") (pin "1") (pinfunction "1_1") (pintype "passive"))
      (node (ref "C27") (pin "1") (pinfunction "1_1") (pintype "passive"))
      (node (ref "C28") (pin "1") (pinfunction "1_1") (pintype "passive"))
      (node (ref "FB4") (pin "2") (pinfunction "2_2") (pintype "passive"))
      (node (ref "U3") (pin "16") (pinfunction "VDD_16") (pintype "power_in"))
      (node (ref "U3") (pin "20") (pinfunction "VCCO1V8_1_20") (pintype "power_in"))
      (node (ref "U3") (pin "29") (pinfunction "VCCO1V8_0_29") (pintype "power_in"))
    )
    (net (code "247") (name "VDD_9") (class "Default")
      (node (ref "C43") (pin "1") (pinfunction "1_1") (pintype "passive"))
      (node (ref "C44") (pin "1") (pinfunction "1_1") (pintype "passive"))
      (node (ref "C45") (pin "1") (pinfunction "1_1") (pintype "passive"))
      (node (ref "C46") (pin "1") (pinfunction "1_1") (pintype "passive"))
      (node (ref "FB7") (pin "2") (pinfunction "2_2") (pintype "passive"))
      (node (ref "U4") (pin "16") (pinfunction "VDD_16") (pintype "power_in"))
      (node (ref "U4") (pin "20") (pinfunction "VCCO1V8_1_20") (pintype "power_in"))
      (node (ref "U4") (pin "29") (pinfunction "VCCO1V8_0_29") (pintype "power_in"))
    )
    (net (code "248") (name "VIN") (class "Default")
      (node (ref "JM1") (pin "97") (pinfunction "97_97") (pintype "bidirectional"))
      (node (ref "JM1") (pin "99") (pinfunction "99_99") (pintype "bidirectional"))
      (node (ref "JP2") (pin "2") (pinfunction "2_2") (pintype "passive"))
    )
    (net (code "249") (name "VSUP") (class "Default")
      (node (ref "JP2") (pin "3") (pinfunction "3_3") (pintype "passive"))
    )
    (net (code "250") (name "VXX") (class "Default")
      (node (ref "C53") (pin "1") (pinfunction "1_1") (pintype "passive"))
      (node (ref "FB17") (pin "2") (pinfunction "2_2") (pintype "passive"))
      (node (ref "U5") (pin "6") (pinfunction "VCC_6") (pintype "power_in"))
    )
    (net (code "251") (name "unconnected-(JP1-Pad1)") (class "Default")
      (node (ref "JP1") (pin "1") (pinfunction "1_1") (pintype "passive"))
    )
    (net (code "252") (name "unconnected-(JP1-Pad2)") (class "Default")
      (node (ref "JP1") (pin "2") (pinfunction "2_2") (pintype "passive"))
    )
    (net (code "253") (name "unconnected-(JP1-Pad3)") (class "Default")
      (node (ref "JP1") (pin "3") (pinfunction "3_3") (pintype "passive"))
    )
    (net (code "254") (name "unconnected-(JP1-Pad4)") (class "Default")
      (node (ref "JP1") (pin "4") (pinfunction "4_4") (pintype "passive"))
    )
    (net (code "255") (name "unconnected-(JP1-Pad5)") (class "Default")
      (node (ref "JP1") (pin "5") (pinfunction "5_5") (pintype "passive"))
    )
    (net (code "256") (name "unconnected-(JP1-Pad6)") (class "Default")
      (node (ref "JP1") (pin "6") (pinfunction "6_6") (pintype "passive"))
    )
    (net (code "257") (name "unconnected-(JP1-Pad7)") (class "Default")
      (node (ref "JP1") (pin "7") (pinfunction "7_7") (pintype "passive"))
    )
    (net (code "258") (name "unconnected-(JP1-Pad8)") (class "Default")
      (node (ref "JP1") (pin "8") (pinfunction "8_8") (pintype "passive"))
    )
    (net (code "259") (name "unconnected-(JP1-Pad9)") (class "Default")
      (node (ref "JP1") (pin "9") (pinfunction "9_9") (pintype "passive"))
    )
    (net (code "260") (name "unconnected-(JP1-Pad10)") (class "Default")
      (node (ref "JP1") (pin "10") (pinfunction "10_10") (pintype "passive"))
    )
    (net (code "261") (name "unconnected-(JP1-Pad11)") (class "Default")
      (node (ref "JP1") (pin "11") (pinfunction "11_11") (pintype "passive"))
    )
    (net (code "262") (name "unconnected-(JP1-Pad12)") (class "Default")
      (node (ref "JP1") (pin "12") (pinfunction "12_12") (pintype "passive"))
    )
    (net (code "263") (name "unconnected-(JP1-Pad13)") (class "Default")
      (node (ref "JP1") (pin "13") (pinfunction "13_13") (pintype "passive"))
    )
    (net (code "264") (name "unconnected-(JP1-Pad14)") (class "Default")
      (node (ref "JP1") (pin "14") (pinfunction "14_14") (pintype "passive"))
    )
    (net (code "265") (name "unconnected-(PCIE-NORTH-PWRGD-PadA11)") (class "Default")
      (node (ref "PCIE-NORTH") (pin "A11") (pinfunction "PWRGD_A11") (pintype "passive"))
    )
    (net (code "266") (name "unconnected-(PCIE-SOUTH-PWRGD-PadA11)") (class "Default")
      (node (ref "PCIE-SOUTH") (pin "A11") (pinfunction "PWRGD_A11") (pintype "passive"))
    )
    (net (code "267") (name "unconnected-(PCIE-SOUTH-SCL-PadB2)") (class "Default")
      (node (ref "PCIE-SOUTH") (pin "B2") (pinfunction "SCL_B2") (pintype "passive"))
    )
    (net (code "268") (name "unconnected-(PCIE-SOUTH-SDA-PadB1)") (class "Default")
      (node (ref "PCIE-SOUTH") (pin "B1") (pinfunction "SDA_B1") (pintype "passive"))
    )
    (net (code "269") (name "unconnected-(PCIE-SOUTH-V_I2C-PadB3)") (class "Default")
      (node (ref "PCIE-SOUTH") (pin "B3") (pinfunction "V_I2C_B3") (pintype "passive"))
    )
  )
)
